# Configuration_Clocking_SRAM.net
KiCad netlist of a schematic drawn in Altium Designer
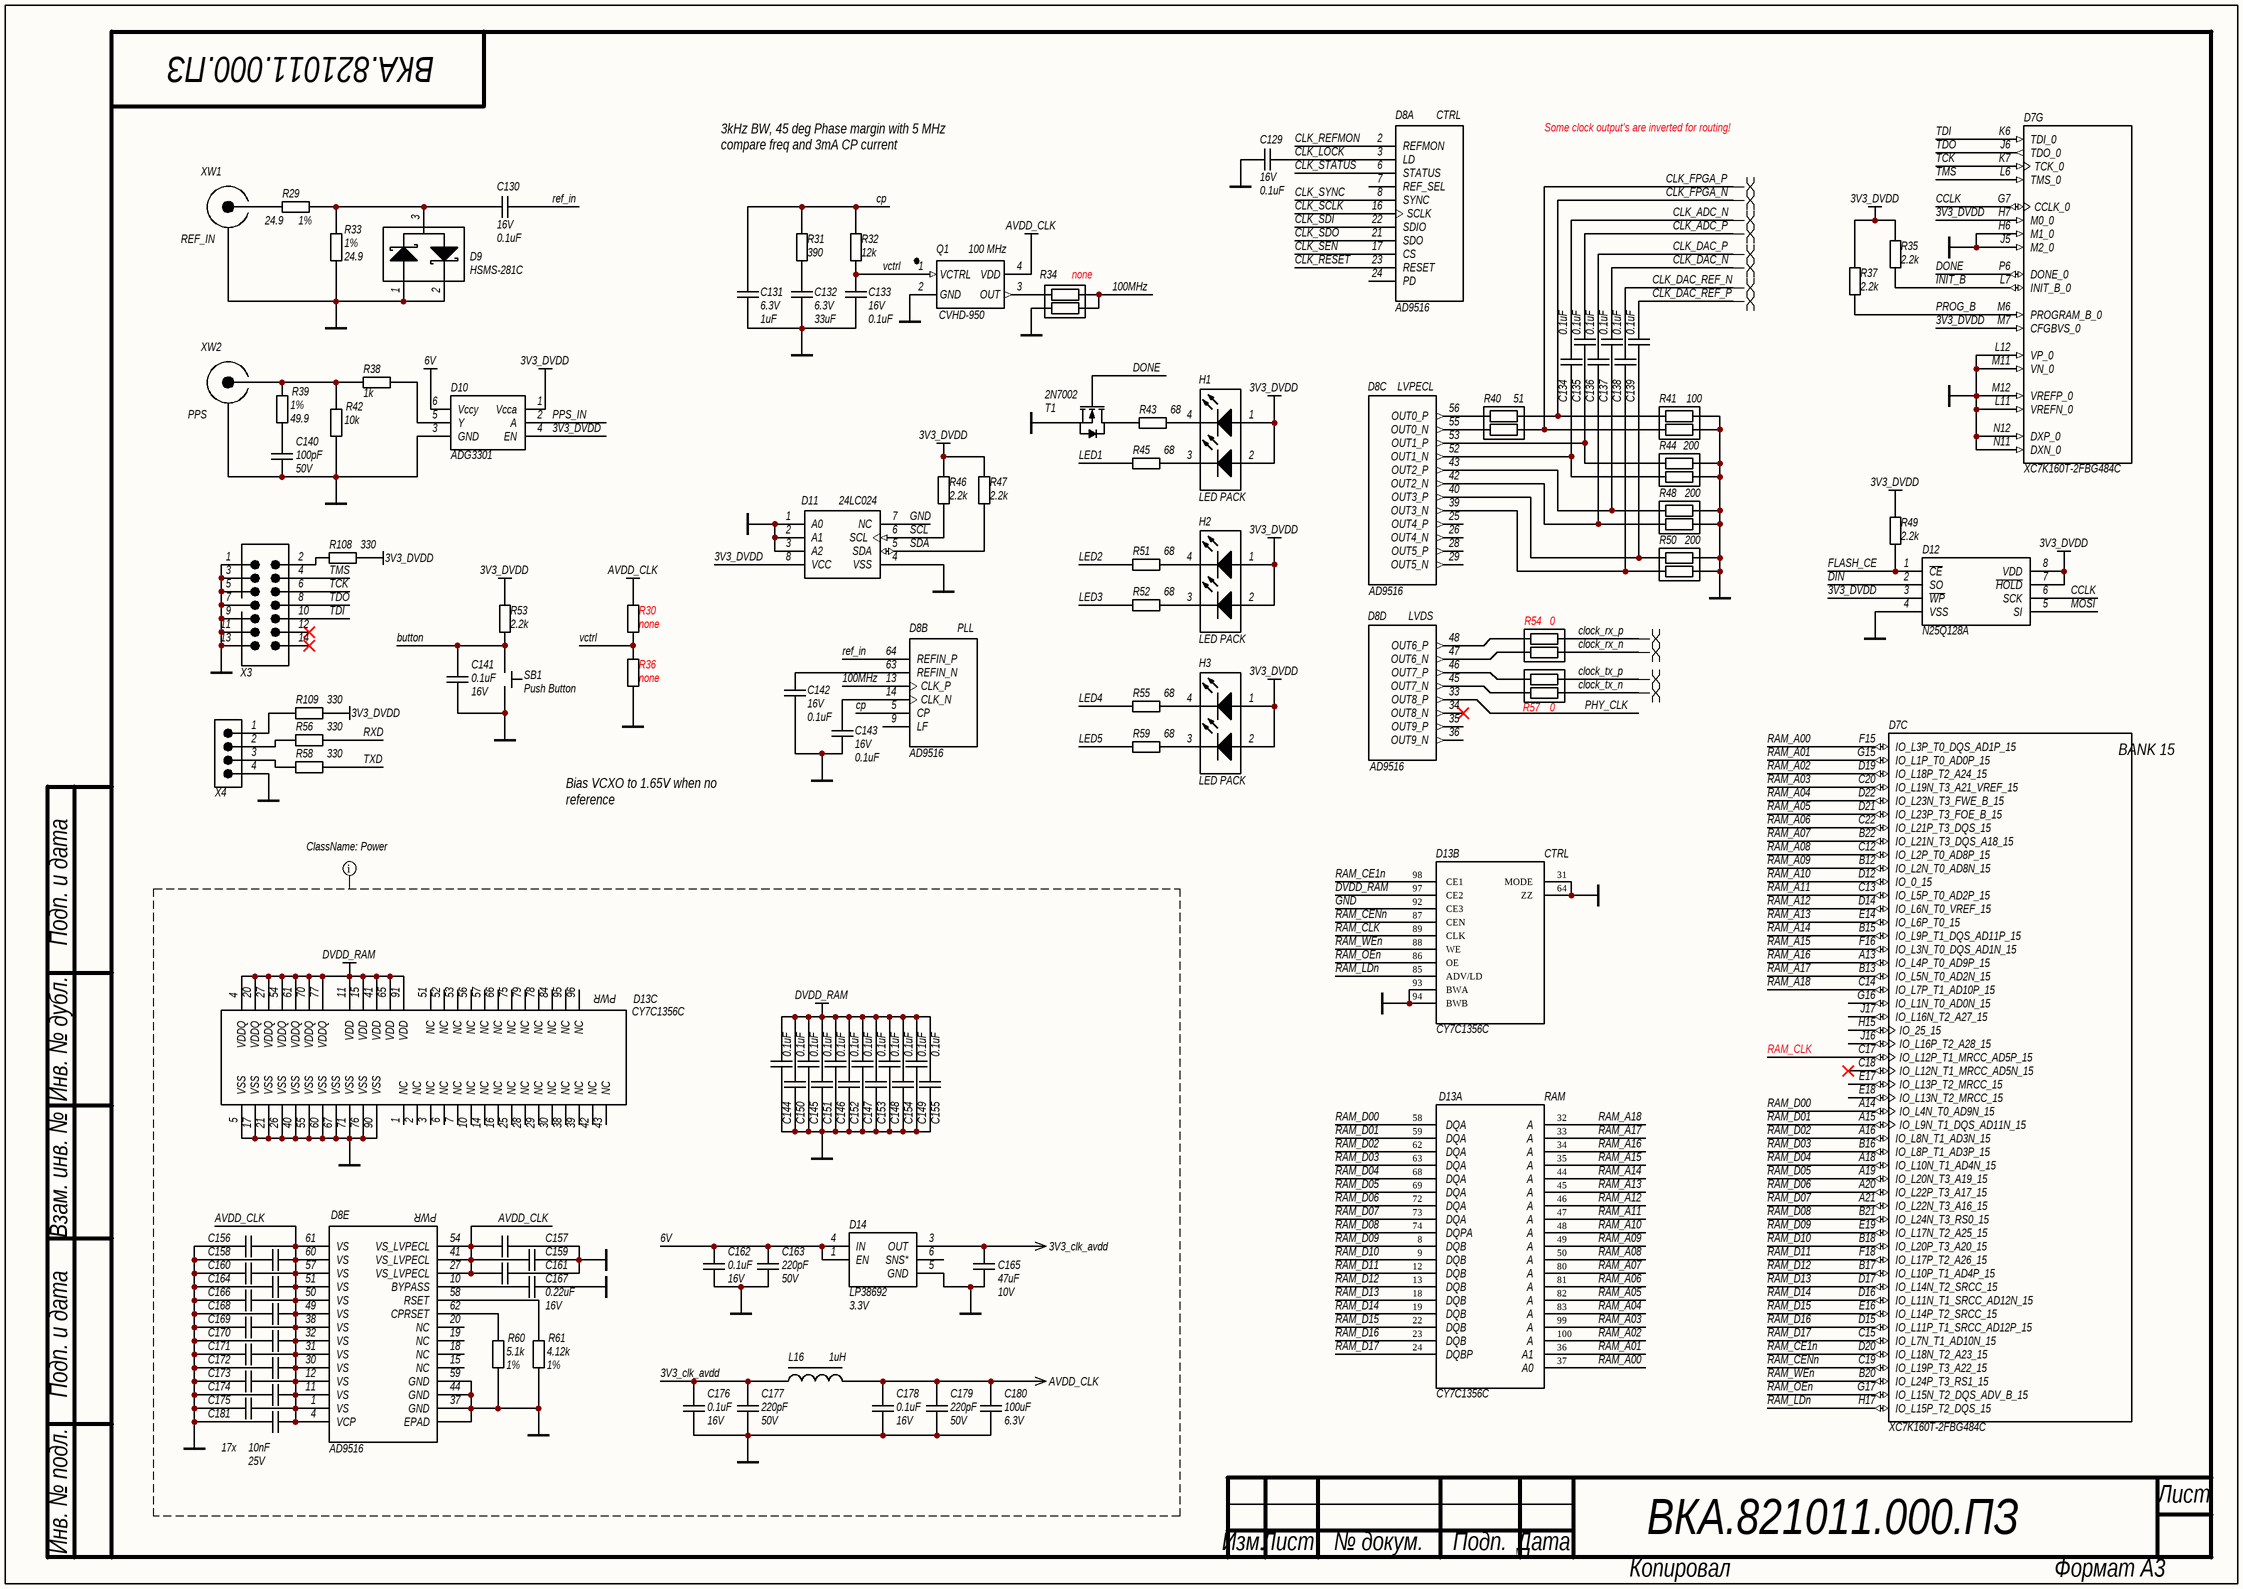
[diagram p0: Configuration&Clocking&SRAM.SchDoc]

(export (version "E")
  (design (tool "Eeschema 10.0.6"))
  (components
    (comp (ref "C129")
      (value "0.1uF")
      (footprint "C0402")
      (description "SMD Capacitor")
      (fields
        (field (name "MANUFACTURER") "Murata")
        (field (name "TOLERANCE") "10%")
        (field (name "VOLTAGE") "16V")
      )
      (libsource (lib "Kintex_SDR") (part "CAP"))
    )
    (comp (ref "C130")
      (value "0.1uF")
      (footprint "C0402")
      (description "SMD Capacitor")
      (fields
        (field (name "MANUFACTURER") "Murata")
        (field (name "TOLERANCE") "10%")
        (field (name "VOLTAGE") "16V")
      )
      (libsource (lib "Kintex_SDR") (part "CAP"))
    )
    (comp (ref "C131")
      (value "1uF")
      (footprint "C0402")
      (description "SMD Capacitor")
      (fields
        (field (name "MANUFACTURER") "Murata")
        (field (name "TOLERANCE") "10%")
        (field (name "VOLTAGE") "6.3V")
      )
      (libsource (lib "Kintex_SDR") (part "CAP"))
    )
    (comp (ref "C132")
      (value "33uF")
      (footprint "C1210")
      (description "SMD Capacitor")
      (fields
        (field (name "MANUFACTURER") "Murata")
        (field (name "TOLERANCE") "10%")
        (field (name "VOLTAGE") "6.3V")
      )
      (libsource (lib "Kintex_SDR") (part "CAP uF"))
    )
    (comp (ref "C133")
      (value "0.1uF")
      (footprint "C0402")
      (description "SMD Capacitor")
      (fields
        (field (name "MANUFACTURER") "Murata")
        (field (name "TOLERANCE") "10%")
        (field (name "VOLTAGE") "16V")
      )
      (libsource (lib "Kintex_SDR") (part "CAP"))
    )
    (comp (ref "C134")
      (value "0.1uF")
      (footprint "C0402")
      (description "SMD Capacitor")
      (fields (field (name "MANUFACTURER") "Murata") (field (name "TOLERANCE") "10%"))
      (libsource (lib "Kintex_SDR") (part "CAP"))
    )
    (comp (ref "C135")
      (value "0.1uF")
      (footprint "C0402")
      (description "SMD Capacitor")
      (fields (field (name "MANUFACTURER") "Murata") (field (name "TOLERANCE") "10%"))
      (libsource (lib "Kintex_SDR") (part "CAP"))
    )
    (comp (ref "C136")
      (value "0.1uF")
      (footprint "C0402")
      (description "SMD Capacitor")
      (fields (field (name "MANUFACTURER") "Murata") (field (name "TOLERANCE") "10%"))
      (libsource (lib "Kintex_SDR") (part "CAP"))
    )
    (comp (ref "C137")
      (value "0.1uF")
      (footprint "C0402")
      (description "SMD Capacitor")
      (fields (field (name "MANUFACTURER") "Murata") (field (name "TOLERANCE") "10%"))
      (libsource (lib "Kintex_SDR") (part "CAP"))
    )
    (comp (ref "C138")
      (value "0.1uF")
      (footprint "C0402")
      (description "SMD Capacitor")
      (fields (field (name "MANUFACTURER") "Murata") (field (name "TOLERANCE") "10%"))
      (libsource (lib "Kintex_SDR") (part "CAP"))
    )
    (comp (ref "C139")
      (value "0.1uF")
      (footprint "C0402")
      (description "SMD Capacitor")
      (fields (field (name "MANUFACTURER") "Murata") (field (name "TOLERANCE") "10%"))
      (libsource (lib "Kintex_SDR") (part "CAP"))
    )
    (comp (ref "C140")
      (value "100pF")
      (footprint "C0603")
      (description "SMD Capacitor")
      (fields
        (field (name "MANUFACTURER") "Murata")
        (field (name "TOLERANCE") "10%")
        (field (name "VOLTAGE") "50V")
      )
      (libsource (lib "Kintex_SDR") (part "CAP"))
    )
    (comp (ref "C141")
      (value "0.1uF")
      (footprint "C0402")
      (description "SMD Capacitor")
      (fields
        (field (name "MANUFACTURER") "Murata")
        (field (name "TOLERANCE") "10%")
        (field (name "VOLTAGE") "16V")
      )
      (libsource (lib "Kintex_SDR") (part "CAP"))
    )
    (comp (ref "C142")
      (value "0.1uF")
      (footprint "C0402")
      (description "SMD Capacitor")
      (fields
        (field (name "MANUFACTURER") "Murata")
        (field (name "TOLERANCE") "10%")
        (field (name "VOLTAGE") "16V")
      )
      (libsource (lib "Kintex_SDR") (part "CAP"))
    )
    (comp (ref "C143")
      (value "0.1uF")
      (footprint "C0402")
      (description "SMD Capacitor")
      (fields
        (field (name "MANUFACTURER") "Murata")
        (field (name "TOLERANCE") "10%")
        (field (name "VOLTAGE") "16V")
      )
      (libsource (lib "Kintex_SDR") (part "CAP"))
    )
    (comp (ref "C144")
      (value "0.1uF")
      (footprint "C0402")
      (description "SMD Capacitor")
      (fields (field (name "MANUFACTURER") "Murata") (field (name "TOLERANCE") "10%"))
      (libsource (lib "Kintex_SDR") (part "CAP"))
    )
    (comp (ref "C145")
      (value "0.1uF")
      (footprint "C0402")
      (description "SMD Capacitor")
      (fields (field (name "MANUFACTURER") "Murata") (field (name "TOLERANCE") "10%"))
      (libsource (lib "Kintex_SDR") (part "CAP"))
    )
    (comp (ref "C146")
      (value "0.1uF")
      (footprint "C0402")
      (description "SMD Capacitor")
      (fields (field (name "MANUFACTURER") "Murata") (field (name "TOLERANCE") "10%"))
      (libsource (lib "Kintex_SDR") (part "CAP"))
    )
    (comp (ref "C147")
      (value "0.1uF")
      (footprint "C0402")
      (description "SMD Capacitor")
      (fields (field (name "MANUFACTURER") "Murata") (field (name "TOLERANCE") "10%"))
      (libsource (lib "Kintex_SDR") (part "CAP"))
    )
    (comp (ref "C148")
      (value "0.1uF")
      (footprint "C0402")
      (description "SMD Capacitor")
      (fields (field (name "MANUFACTURER") "Murata") (field (name "TOLERANCE") "10%"))
      (libsource (lib "Kintex_SDR") (part "CAP"))
    )
    (comp (ref "C149")
      (value "0.1uF")
      (footprint "C0402")
      (description "SMD Capacitor")
      (fields (field (name "MANUFACTURER") "Murata") (field (name "TOLERANCE") "10%"))
      (libsource (lib "Kintex_SDR") (part "CAP"))
    )
    (comp (ref "C150")
      (value "0.1uF")
      (footprint "C0402")
      (description "SMD Capacitor")
      (fields (field (name "MANUFACTURER") "Murata") (field (name "TOLERANCE") "10%"))
      (libsource (lib "Kintex_SDR") (part "CAP"))
    )
    (comp (ref "C151")
      (value "0.1uF")
      (footprint "C0402")
      (description "SMD Capacitor")
      (fields (field (name "MANUFACTURER") "Murata") (field (name "TOLERANCE") "10%"))
      (libsource (lib "Kintex_SDR") (part "CAP"))
    )
    (comp (ref "C152")
      (value "0.1uF")
      (footprint "C0402")
      (description "SMD Capacitor")
      (fields (field (name "MANUFACTURER") "Murata") (field (name "TOLERANCE") "10%"))
      (libsource (lib "Kintex_SDR") (part "CAP"))
    )
    (comp (ref "C153")
      (value "0.1uF")
      (footprint "C0402")
      (description "SMD Capacitor")
      (fields (field (name "MANUFACTURER") "Murata") (field (name "TOLERANCE") "10%"))
      (libsource (lib "Kintex_SDR") (part "CAP"))
    )
    (comp (ref "C154")
      (value "0.1uF")
      (footprint "C0402")
      (description "SMD Capacitor")
      (fields (field (name "MANUFACTURER") "Murata") (field (name "TOLERANCE") "10%"))
      (libsource (lib "Kintex_SDR") (part "CAP"))
    )
    (comp (ref "C155")
      (value "0.1uF")
      (footprint "C0402")
      (description "SMD Capacitor")
      (fields (field (name "MANUFACTURER") "Murata") (field (name "TOLERANCE") "10%"))
      (libsource (lib "Kintex_SDR") (part "CAP"))
    )
    (comp (ref "C156")
      (value "CAP")
      (footprint "C0402")
      (description "SMD Capacitor")
      (fields (field (name "MANUFACTURER") "Murata") (field (name "TOLERANCE") "10%"))
      (libsource (lib "Kintex_SDR") (part "CAP"))
    )
    (comp (ref "C157")
      (value "CAP")
      (footprint "C0402")
      (description "SMD Capacitor")
      (fields (field (name "MANUFACTURER") "Murata") (field (name "TOLERANCE") "10%"))
      (libsource (lib "Kintex_SDR") (part "CAP"))
    )
    (comp (ref "C158")
      (value "CAP")
      (footprint "C0402")
      (description "SMD Capacitor")
      (fields (field (name "MANUFACTURER") "Murata") (field (name "TOLERANCE") "10%"))
      (libsource (lib "Kintex_SDR") (part "CAP"))
    )
    (comp (ref "C159")
      (value "CAP")
      (footprint "C0402")
      (description "SMD Capacitor")
      (fields (field (name "MANUFACTURER") "Murata") (field (name "TOLERANCE") "10%"))
      (libsource (lib "Kintex_SDR") (part "CAP"))
    )
    (comp (ref "C160")
      (value "CAP")
      (footprint "C0402")
      (description "SMD Capacitor")
      (fields (field (name "MANUFACTURER") "Murata") (field (name "TOLERANCE") "10%"))
      (libsource (lib "Kintex_SDR") (part "CAP"))
    )
    (comp (ref "C161")
      (value "CAP")
      (footprint "C0402")
      (description "SMD Capacitor")
      (fields (field (name "MANUFACTURER") "Murata") (field (name "TOLERANCE") "10%"))
      (libsource (lib "Kintex_SDR") (part "CAP"))
    )
    (comp (ref "C162")
      (value "0.1uF")
      (footprint "C0603")
      (description "SMD Capacitor")
      (fields
        (field (name "MANUFACTURER") "Murata")
        (field (name "TOLERANCE") "10%")
        (field (name "VOLTAGE") "16V")
      )
      (libsource (lib "Kintex_SDR") (part "CAP"))
    )
    (comp (ref "C163")
      (value "220pF")
      (footprint "C0603")
      (description "SMD Capacitor")
      (fields
        (field (name "MANUFACTURER") "Murata")
        (field (name "TOLERANCE") "10%")
        (field (name "VOLTAGE") "50V")
      )
      (libsource (lib "Kintex_SDR") (part "CAP"))
    )
    (comp (ref "C164")
      (value "CAP")
      (footprint "C0402")
      (description "SMD Capacitor")
      (fields (field (name "MANUFACTURER") "Murata") (field (name "TOLERANCE") "10%"))
      (libsource (lib "Kintex_SDR") (part "CAP"))
    )
    (comp (ref "C165")
      (value "47uF")
      (footprint "C1210")
      (description "SMD Capacitor")
      (fields
        (field (name "MANUFACTURER") "Murata")
        (field (name "TOLERANCE") "10%")
        (field (name "VOLTAGE") "10V")
      )
      (libsource (lib "Kintex_SDR") (part "CAP uF"))
    )
    (comp (ref "C166")
      (value "CAP")
      (footprint "C0402")
      (description "SMD Capacitor")
      (fields (field (name "MANUFACTURER") "Murata") (field (name "TOLERANCE") "10%"))
      (libsource (lib "Kintex_SDR") (part "CAP"))
    )
    (comp (ref "C167")
      (value "0.22uF")
      (footprint "C0402")
      (description "SMD Capacitor")
      (fields
        (field (name "MANUFACTURER") "Murata")
        (field (name "TOLERANCE") "10%")
        (field (name "VOLTAGE") "16V")
      )
      (libsource (lib "Kintex_SDR") (part "CAP"))
    )
    (comp (ref "C168")
      (value "CAP")
      (footprint "C0402")
      (description "SMD Capacitor")
      (fields (field (name "MANUFACTURER") "Murata") (field (name "TOLERANCE") "10%"))
      (libsource (lib "Kintex_SDR") (part "CAP"))
    )
    (comp (ref "C169")
      (value "CAP")
      (footprint "C0402")
      (description "SMD Capacitor")
      (fields (field (name "MANUFACTURER") "Murata") (field (name "TOLERANCE") "10%"))
      (libsource (lib "Kintex_SDR") (part "CAP"))
    )
    (comp (ref "C170")
      (value "CAP")
      (footprint "C0402")
      (description "SMD Capacitor")
      (fields (field (name "MANUFACTURER") "Murata") (field (name "TOLERANCE") "10%"))
      (libsource (lib "Kintex_SDR") (part "CAP"))
    )
    (comp (ref "C171")
      (value "CAP")
      (footprint "C0402")
      (description "SMD Capacitor")
      (fields (field (name "MANUFACTURER") "Murata") (field (name "TOLERANCE") "10%"))
      (libsource (lib "Kintex_SDR") (part "CAP"))
    )
    (comp (ref "C172")
      (value "CAP")
      (footprint "C0402")
      (description "SMD Capacitor")
      (fields (field (name "MANUFACTURER") "Murata") (field (name "TOLERANCE") "10%"))
      (libsource (lib "Kintex_SDR") (part "CAP"))
    )
    (comp (ref "C173")
      (value "CAP")
      (footprint "C0402")
      (description "SMD Capacitor")
      (fields (field (name "MANUFACTURER") "Murata") (field (name "TOLERANCE") "10%"))
      (libsource (lib "Kintex_SDR") (part "CAP"))
    )
    (comp (ref "C174")
      (value "CAP")
      (footprint "C0402")
      (description "SMD Capacitor")
      (fields (field (name "MANUFACTURER") "Murata") (field (name "TOLERANCE") "10%"))
      (libsource (lib "Kintex_SDR") (part "CAP"))
    )
    (comp (ref "C175")
      (value "CAP")
      (footprint "C0402")
      (description "SMD Capacitor")
      (fields (field (name "MANUFACTURER") "Murata") (field (name "TOLERANCE") "10%"))
      (libsource (lib "Kintex_SDR") (part "CAP"))
    )
    (comp (ref "C176")
      (value "0.1uF")
      (footprint "C0603")
      (description "SMD Capacitor")
      (fields
        (field (name "MANUFACTURER") "Murata")
        (field (name "TOLERANCE") "10%")
        (field (name "VOLTAGE") "16V")
      )
      (libsource (lib "Kintex_SDR") (part "CAP"))
    )
    (comp (ref "C177")
      (value "220pF")
      (footprint "C0603")
      (description "SMD Capacitor")
      (fields
        (field (name "MANUFACTURER") "Murata")
        (field (name "TOLERANCE") "10%")
        (field (name "VOLTAGE") "50V")
      )
      (libsource (lib "Kintex_SDR") (part "CAP"))
    )
    (comp (ref "C178")
      (value "0.1uF")
      (footprint "C0603")
      (description "SMD Capacitor")
      (fields
        (field (name "MANUFACTURER") "Murata")
        (field (name "TOLERANCE") "10%")
        (field (name "VOLTAGE") "16V")
      )
      (libsource (lib "Kintex_SDR") (part "CAP"))
    )
    (comp (ref "C179")
      (value "220pF")
      (footprint "C0603")
      (description "SMD Capacitor")
      (fields
        (field (name "MANUFACTURER") "Murata")
        (field (name "TOLERANCE") "10%")
        (field (name "VOLTAGE") "50V")
      )
      (libsource (lib "Kintex_SDR") (part "CAP"))
    )
    (comp (ref "C180")
      (value "100uF")
      (footprint "C1210")
      (description "SMD Capacitor")
      (fields
        (field (name "MANUFACTURER") "Murata")
        (field (name "TOLERANCE") "20%")
        (field (name "VOLTAGE") "6.3V")
      )
      (libsource (lib "Kintex_SDR") (part "CAP uF"))
    )
    (comp (ref "C181")
      (value "10nF")
      (footprint "C0402")
      (description "SMD Capacitor")
      (fields
        (field (name "MANUFACTURER") "Murata")
        (field (name "TOLERANCE") "10%")
        (field (name "VOLTAGE") "25V")
      )
      (libsource (lib "Kintex_SDR") (part "CAP"))
    )
    (comp (ref "D7")
      (value "XC7K160T-2FBG484C")
      (footprint "FBG484")
      (description "Xilinx 7-Series FPGA")
      (fields (field (name "MANUFACTURER") "Xilinx"))
      (libsource (lib "Kintex_SDR") (part "XC7K160T-2FBG484C"))
    )
    (comp (ref "D8")
      (value "AD9516")
      (footprint "LFCSP-64")
      (description "14-Output Clock Generator")
      (fields (field (name "VOLTAGE") "2.5 V to 3.3 V"))
      (libsource (lib "Kintex_SDR") (part "AD9516"))
    )
    (comp (ref "D9")
      (value "HSMS-281C")
      (footprint "SOT-323")
      (description "RF Schottky Barrier Diodes")
      (libsource (lib "Kintex_SDR") (part "HSMS-281x"))
    )
    (comp (ref "D10")
      (value "ADG3301")
      (footprint "SOT-23-6")
      (description "Bidirectional Logic Level Translator")
      (fields (field (name "VOLTAGE") "1.15 V to 5.5 V"))
      (libsource (lib "Kintex_SDR") (part "ADG3301"))
    )
    (comp (ref "D11")
      (value "24LC024")
      (footprint "SOIC_SN8")
      (description "I2C EEPROM")
      (fields (field (name "MANUFACTURER") "Microchip") (field (name "VOLTAGE") "2.5-5.5V"))
      (libsource (lib "Kintex_SDR") (part "24LC024"))
    )
    (comp (ref "D12")
      (value "N25Q128A")
      (footprint "SOIC8-W")
      (description "SPI Flash")
      (fields (field (name "MANUFACTURER") "Micron Technology") (field (name "VOLTAGE") "2.7-3.6V"))
      (libsource (lib "Kintex_SDR") (part "N25Q128A"))
    )
    (comp (ref "D13")
      (value "CY7C1356C")
      (footprint "TQFP-100")
      (description "Pipelined SRAM with NoBL")
      (fields (field (name "VOLTAGE") "3.3 V"))
      (libsource (lib "Kintex_SDR") (part "CY7C1356C"))
    )
    (comp (ref "D14")
      (value "LP38692")
      (footprint "SOT-223-5")
      (description "Linear Regulator")
      (fields (field (name "VOLTAGE") "3.3V"))
      (libsource (lib "Kintex_SDR") (part "LP38692"))
    )
    (comp (ref "H1")
      (value "LED PACK")
      (footprint "LED_PACK")
      (description "LED Pack For Front Panel")
      (fields (field (name "MANUFACTURER") "Kingbright"))
      (libsource (lib "Kintex_SDR") (part "LED_PACK"))
    )
    (comp (ref "H2")
      (value "LED PACK")
      (footprint "LED_PACK")
      (description "LED Pack For Front Panel")
      (fields (field (name "MANUFACTURER") "Kingbright"))
      (libsource (lib "Kintex_SDR") (part "LED_PACK"))
    )
    (comp (ref "H3")
      (value "LED PACK")
      (footprint "LED_PACK")
      (description "LED Pack For Front Panel")
      (fields (field (name "MANUFACTURER") "Kingbright"))
      (libsource (lib "Kintex_SDR") (part "LED_PACK"))
    )
    (comp (ref "L16")
      (value "1uH")
      (footprint "L1210_Murata")
      (description "Inductor Power Lines")
      (fields (field (name "MANUFACTURER") "Murata") (field (name "TOLERANCE") "5%"))
      (libsource (lib "Kintex_SDR") (part "Inductor LF"))
    )
    (comp (ref "Q1")
      (value "CVHD-950")
      (footprint "CVHD-950")
      (description "Crystal Oscillator")
      (fields (field (name "VOLTAGE") "3.3V ±0.3V") (field (name "FREQUENCY") "100 MHz"))
      (libsource (lib "Kintex_SDR") (part "CVHD-950"))
    )
    (comp (ref "R29")
      (value "24.9")
      (footprint "R0402")
      (description "SMD Resistor")
      (fields
        (field (name "POWER") "0.062 Wt")
        (field (name "TOLERANCE") "1%")
        (field (name "Comment") "RES")
      )
      (libsource (lib "") (part "RES_1"))
    )
    (comp (ref "R30")
      (value "none")
      (footprint "R0402")
      (description "SMD Resistor")
      (fields (field (name "POWER") "0.062 Wt") (field (name "Comment") "RES"))
      (libsource (lib "") (part "RES_2"))
    )
    (comp (ref "R31")
      (value "390")
      (footprint "R0402")
      (description "SMD Resistor")
      (fields (field (name "POWER") "0.062 Wt") (field (name "TOLERANCE") "5%"))
      (libsource (lib "") (part "RES_3"))
    )
    (comp (ref "R32")
      (value "12k")
      (footprint "R0402")
      (description "SMD Resistor")
      (fields (field (name "POWER") "0.062 Wt") (field (name "TOLERANCE") "5%"))
      (libsource (lib "") (part "RES_2"))
    )
    (comp (ref "R33")
      (value "24.9")
      (footprint "R0402")
      (description "SMD Resistor")
      (fields
        (field (name "POWER") "0.062 Wt")
        (field (name "TOLERANCE") "1%")
        (field (name "Comment") "RES")
      )
      (libsource (lib "") (part "RES_2"))
    )
    (comp (ref "R34")
      (value "none")
      (footprint "EX24V")
      (description "Chip Resistor Array")
      (fields (field (name "TOLERANCE") "5%") (field (name "MANUFACTURER") "Panasonic"))
      (libsource (lib "Kintex_SDR") (part "RES 2x0402"))
    )
    (comp (ref "R35")
      (value "2.2k")
      (footprint "R0402")
      (description "SMD Resistor")
      (fields (field (name "POWER") "0.062 Wt") (field (name "TOLERANCE") "5%"))
      (libsource (lib "") (part "RES_2"))
    )
    (comp (ref "R36")
      (value "none")
      (footprint "R0402")
      (description "SMD Resistor")
      (fields (field (name "POWER") "0.062 Wt") (field (name "Comment") "RES"))
      (libsource (lib "") (part "RES_2"))
    )
    (comp (ref "R37")
      (value "2.2k")
      (footprint "R0402")
      (description "SMD Resistor")
      (fields (field (name "POWER") "0.062 Wt") (field (name "TOLERANCE") "5%"))
      (libsource (lib "") (part "RES_2"))
    )
    (comp (ref "R38")
      (value "1k")
      (footprint "R0402")
      (description "SMD Resistor")
      (fields (field (name "POWER") "0.062 Wt") (field (name "TOLERANCE") "5%"))
      (libsource (lib "Kintex_SDR") (part "RES"))
    )
    (comp (ref "R39")
      (value "49.9")
      (footprint "R0402")
      (description "SMD Resistor")
      (fields
        (field (name "POWER") "0.062 Wt")
        (field (name "TOLERANCE") "1%")
        (field (name "Comment") "RES")
      )
      (libsource (lib "") (part "RES_2"))
    )
    (comp (ref "R40")
      (value "51")
      (footprint "EX24V")
      (description "Chip Resistor Array")
      (fields (field (name "TOLERANCE") "5%") (field (name "MANUFACTURER") "Panasonic"))
      (libsource (lib "Kintex_SDR") (part "RES 2x0402"))
    )
    (comp (ref "R41")
      (value "100")
      (footprint "EX24V")
      (description "Chip Resistor Array")
      (fields (field (name "TOLERANCE") "5%") (field (name "MANUFACTURER") "Panasonic"))
      (libsource (lib "Kintex_SDR") (part "RES 2x0402"))
    )
    (comp (ref "R42")
      (value "10k")
      (footprint "R0402")
      (description "SMD Resistor")
      (fields (field (name "POWER") "0.062 Wt") (field (name "TOLERANCE") "5%"))
      (libsource (lib "") (part "RES_2"))
    )
    (comp (ref "R43")
      (value "68")
      (footprint "R0402")
      (description "SMD Resistor")
      (fields (field (name "POWER") "0.062 Wt") (field (name "TOLERANCE") "5%"))
      (libsource (lib "Kintex_SDR") (part "RES"))
    )
    (comp (ref "R44")
      (value "200")
      (footprint "EX24V")
      (description "Chip Resistor Array")
      (fields (field (name "TOLERANCE") "5%") (field (name "MANUFACTURER") "Panasonic"))
      (libsource (lib "") (part "RES 2x0402_1"))
    )
    (comp (ref "R45")
      (value "68")
      (footprint "R0402")
      (description "SMD Resistor")
      (fields (field (name "POWER") "0.062 Wt") (field (name "TOLERANCE") "5%"))
      (libsource (lib "Kintex_SDR") (part "RES"))
    )
    (comp (ref "R46")
      (value "2.2k")
      (footprint "R0402")
      (description "SMD Resistor")
      (fields (field (name "POWER") "0.062 Wt") (field (name "TOLERANCE") "5%"))
      (libsource (lib "") (part "RES_2"))
    )
    (comp (ref "R47")
      (value "2.2k")
      (footprint "R0402")
      (description "SMD Resistor")
      (fields (field (name "POWER") "0.062 Wt") (field (name "TOLERANCE") "5%"))
      (libsource (lib "") (part "RES_2"))
    )
    (comp (ref "R48")
      (value "200")
      (footprint "EX24V")
      (description "Chip Resistor Array")
      (fields (field (name "TOLERANCE") "5%") (field (name "MANUFACTURER") "Panasonic"))
      (libsource (lib "") (part "RES 2x0402_1"))
    )
    (comp (ref "R49")
      (value "2.2k")
      (footprint "R0402")
      (description "SMD Resistor")
      (fields (field (name "POWER") "0.062 Wt") (field (name "TOLERANCE") "5%"))
      (libsource (lib "") (part "RES_2"))
    )
    (comp (ref "R50")
      (value "200")
      (footprint "EX24V")
      (description "Chip Resistor Array")
      (fields (field (name "TOLERANCE") "5%") (field (name "MANUFACTURER") "Panasonic"))
      (libsource (lib "") (part "RES 2x0402_1"))
    )
    (comp (ref "R51")
      (value "68")
      (footprint "R0402")
      (description "SMD Resistor")
      (fields (field (name "POWER") "0.062 Wt") (field (name "TOLERANCE") "5%"))
      (libsource (lib "Kintex_SDR") (part "RES"))
    )
    (comp (ref "R52")
      (value "68")
      (footprint "R0402")
      (description "SMD Resistor")
      (fields (field (name "POWER") "0.062 Wt") (field (name "TOLERANCE") "5%"))
      (libsource (lib "Kintex_SDR") (part "RES"))
    )
    (comp (ref "R53")
      (value "2.2k")
      (footprint "R0402")
      (description "SMD Resistor")
      (fields (field (name "POWER") "0.062 Wt") (field (name "TOLERANCE") "5%"))
      (libsource (lib "") (part "RES_2"))
    )
    (comp (ref "R54")
      (value "0")
      (footprint "EX24V")
      (description "Chip Resistor Array")
      (fields (field (name "MANUFACTURER") "Panasonic") (field (name "Comment") "RES 2x0402"))
      (libsource (lib "Kintex_SDR") (part "RES 2x0402"))
    )
    (comp (ref "R55")
      (value "68")
      (footprint "R0402")
      (description "SMD Resistor")
      (fields (field (name "POWER") "0.062 Wt") (field (name "TOLERANCE") "5%"))
      (libsource (lib "Kintex_SDR") (part "RES"))
    )
    (comp (ref "R56")
      (value "330")
      (footprint "R0402")
      (description "SMD Resistor")
      (fields (field (name "POWER") "0.062 Wt") (field (name "TOLERANCE") "5%"))
      (libsource (lib "Kintex_SDR") (part "RES"))
    )
    (comp (ref "R57")
      (value "0")
      (footprint "EX24V")
      (description "Chip Resistor Array")
      (fields (field (name "MANUFACTURER") "Panasonic") (field (name "Comment") "RES 2x0402"))
      (libsource (lib "Kintex_SDR") (part "RES 2x0402"))
    )
    (comp (ref "R58")
      (value "330")
      (footprint "R0402")
      (description "SMD Resistor")
      (fields (field (name "POWER") "0.062 Wt") (field (name "TOLERANCE") "5%"))
      (libsource (lib "Kintex_SDR") (part "RES"))
    )
    (comp (ref "R59")
      (value "68")
      (footprint "R0402")
      (description "SMD Resistor")
      (fields (field (name "POWER") "0.062 Wt") (field (name "TOLERANCE") "5%"))
      (libsource (lib "Kintex_SDR") (part "RES"))
    )
    (comp (ref "R60")
      (value "5.1k")
      (footprint "R0402")
      (description "SMD Resistor")
      (fields
        (field (name "POWER") "0.062 Wt")
        (field (name "TOLERANCE") "1%")
        (field (name "Comment") "RES")
      )
      (libsource (lib "") (part "RES_2"))
    )
    (comp (ref "R61")
      (value "4.12k")
      (footprint "R0402")
      (description "SMD Resistor")
      (fields
        (field (name "POWER") "0.062 Wt")
        (field (name "TOLERANCE") "1%")
        (field (name "Comment") "RES")
      )
      (libsource (lib "") (part "RES_2"))
    )
    (comp (ref "R108")
      (value "330")
      (footprint "R0402")
      (description "SMD Resistor")
      (fields (field (name "POWER") "0.062 Wt") (field (name "TOLERANCE") "5%"))
      (libsource (lib "Kintex_SDR") (part "RES"))
    )
    (comp (ref "R109")
      (value "330")
      (footprint "R0402")
      (description "SMD Resistor")
      (fields (field (name "POWER") "0.062 Wt") (field (name "TOLERANCE") "5%"))
      (libsource (lib "Kintex_SDR") (part "RES"))
    )
    (comp (ref "SB1")
      (value "Push Button")
      (footprint "B3FS-1000")
      (description "Tactile Switch (SMT)")
      (fields (field (name "MANUFACTURER") "Omron") (field (name "VOLTAGE") "24V"))
      (libsource (lib "Kintex_SDR") (part "Button"))
    )
    (comp (ref "T1")
      (value "2N7002")
      (footprint "SOT-23")
      (description "N-Channel MOSFET 2N7002")
      (fields (field (name "VOLTAGE") "60V"))
      (libsource (lib "Kintex_SDR") (part "2N7002"))
    )
    (comp (ref "X3")
      (value "HDR Debug_14-pin")
      (footprint "JTAG Header 14-pin")
      (description "14-pin 2.54mm pitch PCB Header")
      (libsource (lib "Kintex_SDR") (part "HDR Debug_14-pin"))
    )
    (comp (ref "X4")
      (value "HDR 4-way")
      (footprint "Right Angle Male Header")
      (description "4-way Angle PCB Header")
      (libsource (lib "Kintex_SDR") (part "HDR 4-way"))
    )
    (comp (ref "XW1")
      (value "REF_IN")
      (footprint "SMA Angle Female")
      (description "SMA Male Right-Angle PCM Connector")
      (fields (field (name "MANUFACTURER") "Molex"))
      (libsource (lib "Kintex_SDR") (part "SMA RF Connector"))
    )
    (comp (ref "XW2")
      (value "PPS")
      (footprint "SMA Angle Female")
      (description "SMA Male Right-Angle PCM Connector")
      (fields (field (name "MANUFACTURER") "Molex"))
      (libsource (lib "Kintex_SDR") (part "SMA RF Connector"))
    )
  )
  (nets
    (net (code "1") (name "/100MHz") (class "Default")
      (node (ref "D8") (pin "13") (pinfunction "CLK_P_13") (pintype "passive"))
      (node (ref "R34") (pin "3") (pinfunction "3_3") (pintype "passive"))
      (node (ref "R34") (pin "4") (pinfunction "4_4") (pintype "passive"))
    )
    (net (code "2") (name "/CCLK") (class "Default")
      (node (ref "D12") (pin "6") (pinfunction "SCK_6") (pintype "passive"))
      (node (ref "D7") (pin "G7") (pinfunction "CCLK_0_G7") (pintype "bidirectional"))
    )
    (net (code "3") (name "/CLK_ADC_N") (class "Default")
      (node (ref "C134") (pin "1") (pinfunction "1_1") (pintype "passive"))
    )
    (net (code "4") (name "/CLK_ADC_P") (class "Default")
      (node (ref "C135") (pin "1") (pinfunction "1_1") (pintype "passive"))
    )
    (net (code "5") (name "/CLK_DAC_N") (class "Default")
      (node (ref "C137") (pin "1") (pinfunction "1_1") (pintype "passive"))
    )
    (net (code "6") (name "/CLK_DAC_P") (class "Default")
      (node (ref "C136") (pin "1") (pinfunction "1_1") (pintype "passive"))
    )
    (net (code "7") (name "/CLK_DAC_REF_N") (class "Default")
      (node (ref "C138") (pin "1") (pinfunction "1_1") (pintype "passive"))
    )
    (net (code "8") (name "/CLK_DAC_REF_P") (class "Default")
      (node (ref "C139") (pin "1") (pinfunction "1_1") (pintype "passive"))
    )
    (net (code "9") (name "/CLK_FPGA_N") (class "Default")
      (node (ref "R40") (pin "4") (pinfunction "4_4") (pintype "passive"))
      (node (ref "R41") (pin "1") (pinfunction "1_1") (pintype "passive"))
    )
    (net (code "10") (name "/CLK_FPGA_P") (class "Default")
      (node (ref "R40") (pin "3") (pinfunction "3_3") (pintype "passive"))
      (node (ref "R41") (pin "2") (pinfunction "2_2") (pintype "passive"))
    )
    (net (code "11") (name "/CLK_LOCK") (class "Default")
      (node (ref "C129") (pin "1") (pinfunction "1_1") (pintype "passive"))
      (node (ref "D8") (pin "3") (pinfunction "LD_3") (pintype "passive"))
    )
    (net (code "12") (name "/CLK_REFMON") (class "Default")
      (node (ref "D8") (pin "2") (pinfunction "REFMON_2") (pintype "passive"))
    )
    (net (code "13") (name "/CLK_RESET") (class "Default")
      (node (ref "D8") (pin "23") (pinfunction "RESET_23") (pintype "passive"))
    )
    (net (code "14") (name "/CLK_SCLK") (class "Default")
      (node (ref "D8") (pin "16") (pinfunction "SCLK_16") (pintype "passive"))
    )
    (net (code "15") (name "/CLK_SDI") (class "Default")
      (node (ref "D8") (pin "22") (pinfunction "SDIO_22") (pintype "passive"))
    )
    (net (code "16") (name "/CLK_SDO") (class "Default")
      (node (ref "D8") (pin "21") (pinfunction "SDO_21") (pintype "passive"))
    )
    (net (code "17") (name "/CLK_SEN") (class "Default")
      (node (ref "D8") (pin "17") (pinfunction "CS_17") (pintype "passive"))
    )
    (net (code "18") (name "/CLK_STATUS") (class "Default")
      (node (ref "D8") (pin "6") (pinfunction "STATUS_6") (pintype "passive"))
    )
    (net (code "19") (name "/CLK_SYNC") (class "Default")
      (node (ref "D8") (pin "8") (pinfunction "SYNC_8") (pintype "passive"))
    )
    (net (code "20") (name "/DIN") (class "Default")
      (node (ref "D12") (pin "2") (pinfunction "SO_2") (pintype "passive"))
    )
    (net (code "21") (name "/DONE") (class "Default")
      (node (ref "D7") (pin "P6") (pinfunction "DONE_0_P6") (pintype "bidirectional"))
      (node (ref "T1") (pin "1") (pinfunction "G_1") (pintype "passive"))
    )
    (net (code "22") (name "/FLASH_CE") (class "Default")
      (node (ref "D12") (pin "1") (pinfunction "~{CE}_1") (pintype "passive"))
      (node (ref "R49") (pin "1") (pinfunction "1_1") (pintype "passive"))
    )
    (net (code "23") (name "/INIT_B") (class "Default")
      (node (ref "D7") (pin "L7") (pinfunction "INIT_B_0_L7") (pintype "bidirectional"))
      (node (ref "R35") (pin "1") (pinfunction "1_1") (pintype "passive"))
    )
    (net (code "24") (name "/LED1") (class "Default")
      (node (ref "R45") (pin "2") (pinfunction "2_2") (pintype "passive"))
    )
    (net (code "25") (name "/LED2") (class "Default")
      (node (ref "R51") (pin "2") (pinfunction "2_2") (pintype "passive"))
    )
    (net (code "26") (name "/LED3") (class "Default")
      (node (ref "R52") (pin "2") (pinfunction "2_2") (pintype "passive"))
    )
    (net (code "27") (name "/LED4") (class "Default")
      (node (ref "R55") (pin "2") (pinfunction "2_2") (pintype "passive"))
    )
    (net (code "28") (name "/LED5") (class "Default")
      (node (ref "R59") (pin "2") (pinfunction "2_2") (pintype "passive"))
    )
    (net (code "29") (name "/MOSI") (class "Default")
      (node (ref "D12") (pin "5") (pinfunction "SI_5") (pintype "passive"))
    )
    (net (code "30") (name "/PHY_CLK") (class "Default")
      (node (ref "D8") (pin "33") (pinfunction "OUT8_P_33") (pintype "output"))
    )
    (net (code "31") (name "/PPS_IN") (class "Default")
      (node (ref "D10") (pin "2") (pinfunction "A_2") (pintype "passive"))
    )
    (net (code "32") (name "/PROG_B") (class "Default")
      (node (ref "D7") (pin "M6") (pinfunction "PROGRAM_B_0_M6") (pintype "input"))
      (node (ref "R37") (pin "1") (pinfunction "1_1") (pintype "passive"))
    )
    (net (code "33") (name "/RAM_A00") (class "Default")
      (node (ref "D13") (pin "37") (pinfunction "A0_37") (pintype "passive"))
      (node (ref "D7") (pin "F15") (pinfunction "IO_L3P_T0_DQS_AD1P_15_F15") (pintype "bidirectional"))
    )
    (net (code "34") (name "/RAM_A01") (class "Default")
      (node (ref "D13") (pin "36") (pinfunction "A1_36") (pintype "passive"))
      (node (ref "D7") (pin "G15") (pinfunction "IO_L1P_T0_AD0P_15_G15") (pintype "bidirectional"))
    )
    (net (code "35") (name "/RAM_A02") (class "Default")
      (node (ref "D13") (pin "100") (pinfunction "A_100") (pintype "passive"))
      (node (ref "D7") (pin "D19") (pinfunction "IO_L18P_T2_A24_15_D19") (pintype "bidirectional"))
    )
    (net (code "36") (name "/RAM_A03") (class "Default")
      (node (ref "D13") (pin "99") (pinfunction "A_99") (pintype "passive"))
      (node (ref "D7") (pin "C20") (pinfunction "IO_L19N_T3_A21_VREF_15_C20") (pintype "bidirectional"))
    )
    (net (code "37") (name "/RAM_A04") (class "Default")
      (node (ref "D13") (pin "83") (pinfunction "A_83") (pintype "passive"))
      (node (ref "D7") (pin "D22") (pinfunction "IO_L23N_T3_FWE_B_15_D22") (pintype "bidirectional"))
    )
    (net (code "38") (name "/RAM_A05") (class "Default")
      (node (ref "D13") (pin "82") (pinfunction "A_82") (pintype "passive"))
      (node (ref "D7") (pin "D21") (pinfunction "IO_L23P_T3_FOE_B_15_D21") (pintype "bidirectional"))
    )
    (net (code "39") (name "/RAM_A06") (class "Default")
      (node (ref "D13") (pin "81") (pinfunction "A_81") (pintype "passive"))
      (node (ref "D7") (pin "C22") (pinfunction "IO_L21P_T3_DQS_15_C22") (pintype "bidirectional"))
    )
    (net (code "40") (name "/RAM_A07") (class "Default")
      (node (ref "D13") (pin "80") (pinfunction "A_80") (pintype "passive"))
      (node (ref "D7") (pin "B22") (pinfunction "IO_L21N_T3_DQS_A18_15_B22") (pintype "bidirectional"))
    )
    (net (code "41") (name "/RAM_A08") (class "Default")
      (node (ref "D13") (pin "50") (pinfunction "A_50") (pintype "passive"))
      (node (ref "D7") (pin "C12") (pinfunction "IO_L2P_T0_AD8P_15_C12") (pintype "bidirectional"))
    )
    (net (code "42") (name "/RAM_A09") (class "Default")
      (node (ref "D13") (pin "49") (pinfunction "A_49") (pintype "passive"))
      (node (ref "D7") (pin "B12") (pinfunction "IO_L2N_T0_AD8N_15_B12") (pintype "bidirectional"))
    )
    (net (code "43") (name "/RAM_A10") (class "Default")
      (node (ref "D13") (pin "48") (pinfunction "A_48") (pintype "passive"))
      (node (ref "D7") (pin "D12") (pinfunction "IO_0_15_D12") (pintype "bidirectional"))
    )
    (net (code "44") (name "/RAM_A11") (class "Default")
      (node (ref "D13") (pin "47") (pinfunction "A_47") (pintype "passive"))
      (node (ref "D7") (pin "C13") (pinfunction "IO_L5P_T0_AD2P_15_C13") (pintype "bidirectional"))
    )
    (net (code "45") (name "/RAM_A12") (class "Default")
      (node (ref "D13") (pin "46") (pinfunction "A_46") (pintype "passive"))
      (node (ref "D7") (pin "D14") (pinfunction "IO_L6N_T0_VREF_15_D14") (pintype "bidirectional"))
    )
    (net (code "46") (name "/RAM_A13") (class "Default")
      (node (ref "D13") (pin "45") (pinfunction "A_45") (pintype "passive"))
      (node (ref "D7") (pin "E14") (pinfunction "IO_L6P_T0_15_E14") (pintype "bidirectional"))
    )
    (net (code "47") (name "/RAM_A14") (class "Default")
      (node (ref "D13") (pin "44") (pinfunction "A_44") (pintype "passive"))
      (node (ref "D7") (pin "B15") (pinfunction "IO_L9P_T1_DQS_AD11P_15_B15") (pintype "bidirectional"))
    )
    (net (code "48") (name "/RAM_A15") (class "Default")
      (node (ref "D13") (pin "35") (pinfunction "A_35") (pintype "passive"))
      (node (ref "D7") (pin "F16") (pinfunction "IO_L3N_T0_DQS_AD1N_15_F16") (pintype "bidirectional"))
    )
    (net (code "49") (name "/RAM_A16") (class "Default")
      (node (ref "D13") (pin "34") (pinfunction "A_34") (pintype "passive"))
      (node (ref "D7") (pin "A13") (pinfunction "IO_L4P_T0_AD9P_15_A13") (pintype "bidirectional"))
    )
    (net (code "50") (name "/RAM_A17") (class "Default")
      (node (ref "D13") (pin "33") (pinfunction "A_33") (pintype "passive"))
      (node (ref "D7") (pin "B13") (pinfunction "IO_L5N_T0_AD2N_15_B13") (pintype "bidirectional"))
    )
    (net (code "51") (name "/RAM_A18") (class "Default")
      (node (ref "D13") (pin "32") (pinfunction "A_32") (pintype "passive"))
      (node (ref "D7") (pin "C14") (pinfunction "IO_L7P_T1_AD10P_15_C14") (pintype "bidirectional"))
    )
    (net (code "52") (name "/RAM_CE1n") (class "Default")
      (node (ref "D13") (pin "98") (pinfunction "CE1_98") (pintype "passive"))
      (node (ref "D7") (pin "D20") (pinfunction "IO_L18N_T2_A23_15_D20") (pintype "bidirectional"))
    )
    (net (code "53") (name "/RAM_CENn") (class "Default")
      (node (ref "D13") (pin "87") (pinfunction "CEN_87") (pintype "passive"))
      (node (ref "D7") (pin "C19") (pinfunction "IO_L19P_T3_A22_15_C19") (pintype "bidirectional"))
    )
    (net (code "54") (name "/RAM_CLK") (class "Default")
      (node (ref "D13") (pin "89") (pinfunction "CLK_89") (pintype "passive"))
      (node (ref "D7") (pin "C17") (pinfunction "IO_L12P_T1_MRCC_AD5P_15_C17") (pintype "bidirectional"))
    )
    (net (code "55") (name "/RAM_D00") (class "Default")
      (node (ref "D13") (pin "58") (pinfunction "DQA_58") (pintype "passive"))
      (node (ref "D7") (pin "A14") (pinfunction "IO_L4N_T0_AD9N_15_A14") (pintype "bidirectional"))
    )
    (net (code "56") (name "/RAM_D01") (class "Default")
      (node (ref "D13") (pin "59") (pinfunction "DQA_59") (pintype "passive"))
      (node (ref "D7") (pin "A15") (pinfunction "IO_L9N_T1_DQS_AD11N_15_A15") (pintype "bidirectional"))
    )
    (net (code "57") (name "/RAM_D02") (class "Default")
      (node (ref "D13") (pin "62") (pinfunction "DQA_62") (pintype "passive"))
      (node (ref "D7") (pin "A16") (pinfunction "IO_L8N_T1_AD3N_15_A16") (pintype "bidirectional"))
    )
    (net (code "58") (name "/RAM_D03") (class "Default")
      (node (ref "D13") (pin "63") (pinfunction "DQA_63") (pintype "passive"))
      (node (ref "D7") (pin "B16") (pinfunction "IO_L8P_T1_AD3P_15_B16") (pintype "bidirectional"))
    )
    (net (code "59") (name "/RAM_D04") (class "Default")
      (node (ref "D13") (pin "68") (pinfunction "DQA_68") (pintype "passive"))
      (node (ref "D7") (pin "A18") (pinfunction "IO_L10N_T1_AD4N_15_A18") (pintype "bidirectional"))
    )
    (net (code "60") (name "/RAM_D05") (class "Default")
      (node (ref "D13") (pin "69") (pinfunction "DQA_69") (pintype "passive"))
      (node (ref "D7") (pin "A19") (pinfunction "IO_L20N_T3_A19_15_A19") (pintype "bidirectional"))
    )
    (net (code "61") (name "/RAM_D06") (class "Default")
      (node (ref "D13") (pin "72") (pinfunction "DQA_72") (pintype "passive"))
      (node (ref "D7") (pin "A20") (pinfunction "IO_L22P_T3_A17_15_A20") (pintype "bidirectional"))
    )
    (net (code "62") (name "/RAM_D07") (class "Default")
      (node (ref "D13") (pin "73") (pinfunction "DQA_73") (pintype "passive"))
      (node (ref "D7") (pin "A21") (pinfunction "IO_L22N_T3_A16_15_A21") (pintype "bidirectional"))
    )
    (net (code "63") (name "/RAM_D08") (class "Default")
      (node (ref "D13") (pin "74") (pinfunction "DQPA_74") (pintype "passive"))
      (node (ref "D7") (pin "B21") (pinfunction "IO_L24N_T3_RS0_15_B21") (pintype "bidirectional"))
    )
    (net (code "64") (name "/RAM_D09") (class "Default")
      (node (ref "D13") (pin "8") (pinfunction "DQB_8") (pintype "passive"))
      (node (ref "D7") (pin "E19") (pinfunction "IO_L17N_T2_A25_15_E19") (pintype "bidirectional"))
    )
    (net (code "65") (name "/RAM_D10") (class "Default")
      (node (ref "D13") (pin "9") (pinfunction "DQB_9") (pintype "passive"))
      (node (ref "D7") (pin "B18") (pinfunction "IO_L20P_T3_A20_15_B18") (pintype "bidirectional"))
    )
    (net (code "66") (name "/RAM_D11") (class "Default")
      (node (ref "D13") (pin "12") (pinfunction "DQB_12") (pintype "passive"))
      (node (ref "D7") (pin "F18") (pinfunction "IO_L17P_T2_A26_15_F18") (pintype "bidirectional"))
    )
    (net (code "67") (name "/RAM_D12") (class "Default")
      (node (ref "D13") (pin "13") (pinfunction "DQB_13") (pintype "passive"))
      (node (ref "D7") (pin "B17") (pinfunction "IO_L10P_T1_AD4P_15_B17") (pintype "bidirectional"))
    )
    (net (code "68") (name "/RAM_D13") (class "Default")
      (node (ref "D13") (pin "18") (pinfunction "DQB_18") (pintype "passive"))
      (node (ref "D7") (pin "D17") (pinfunction "IO_L14N_T2_SRCC_15_D17") (pintype "bidirectional"))
    )
    (net (code "69") (name "/RAM_D14") (class "Default")
      (node (ref "D13") (pin "19") (pinfunction "DQB_19") (pintype "passive"))
      (node (ref "D7") (pin "D16") (pinfunction "IO_L11N_T1_SRCC_AD12N_15_D16") (pintype "bidirectional"))
    )
    (net (code "70") (name "/RAM_D15") (class "Default")
      (node (ref "D13") (pin "22") (pinfunction "DQB_22") (pintype "passive"))
      (node (ref "D7") (pin "E16") (pinfunction "IO_L14P_T2_SRCC_15_E16") (pintype "bidirectional"))
    )
    (net (code "71") (name "/RAM_D16") (class "Default")
      (node (ref "D13") (pin "23") (pinfunction "DQB_23") (pintype "passive"))
      (node (ref "D7") (pin "D15") (pinfunction "IO_L11P_T1_SRCC_AD12P_15_D15") (pintype "bidirectional"))
    )
    (net (code "72") (name "/RAM_D17") (class "Default")
      (node (ref "D13") (pin "24") (pinfunction "DQBP_24") (pintype "passive"))
      (node (ref "D7") (pin "C15") (pinfunction "IO_L7N_T1_AD10N_15_C15") (pintype "bidirectional"))
    )
    (net (code "73") (name "/RAM_LDn") (class "Default")
      (node (ref "D13") (pin "85") (pinfunction "ADV/LD_85") (pintype "passive"))
      (node (ref "D7") (pin "H17") (pinfunction "IO_L15P_T2_DQS_15_H17") (pintype "bidirectional"))
    )
    (net (code "74") (name "/RAM_OEn") (class "Default")
      (node (ref "D13") (pin "86") (pinfunction "OE_86") (pintype "passive"))
      (node (ref "D7") (pin "G17") (pinfunction "IO_L15N_T2_DQS_ADV_B_15_G17") (pintype "bidirectional"))
    )
    (net (code "75") (name "/RAM_WEn") (class "Default")
      (node (ref "D13") (pin "88") (pinfunction "WE_88") (pintype "passive"))
      (node (ref "D7") (pin "B20") (pinfunction "IO_L24P_T3_RS1_15_B20") (pintype "bidirectional"))
    )
    (net (code "76") (name "/RXD") (class "Default")
      (node (ref "R56") (pin "1") (pinfunction "1_1") (pintype "passive"))
    )
    (net (code "77") (name "/SCL") (class "Default")
      (node (ref "D11") (pin "6") (pinfunction "SCL_6") (pintype "input"))
      (node (ref "R46") (pin "1") (pinfunction "1_1") (pintype "passive"))
    )
    (net (code "78") (name "/SDA") (class "Default")
      (node (ref "D11") (pin "5") (pinfunction "SDA_5") (pintype "bidirectional"))
      (node (ref "R47") (pin "1") (pinfunction "1_1") (pintype "passive"))
    )
    (net (code "79") (name "/TCK") (class "Default")
      (node (ref "D7") (pin "K7") (pinfunction "TCK_0_K7") (pintype "input"))
      (node (ref "X3") (pin "6") (pinfunction "TCK_6") (pintype "passive"))
    )
    (net (code "80") (name "/TDI") (class "Default")
      (node (ref "D7") (pin "K6") (pinfunction "TDI_0_K6") (pintype "input"))
      (node (ref "X3") (pin "10") (pinfunction "TDI_10") (pintype "passive"))
    )
    (net (code "81") (name "/TDO") (class "Default")
      (node (ref "D7") (pin "J6") (pinfunction "TDO_0_J6") (pintype "output"))
      (node (ref "X3") (pin "8") (pinfunction "TDO_8") (pintype "passive"))
    )
    (net (code "82") (name "/TMS") (class "Default")
      (node (ref "D7") (pin "L6") (pinfunction "TMS_0_L6") (pintype "input"))
      (node (ref "X3") (pin "4") (pinfunction "TMS_4") (pintype "passive"))
    )
    (net (code "83") (name "/TXD") (class "Default")
      (node (ref "R58") (pin "1") (pinfunction "1_1") (pintype "passive"))
    )
    (net (code "84") (name "/button") (class "Default")
      (node (ref "C141") (pin "2") (pinfunction "2_2") (pintype "passive"))
      (node (ref "R53") (pin "1") (pinfunction "1_1") (pintype "passive"))
      (node (ref "SB1") (pin "1") (pinfunction "1_1") (pintype "passive"))
    )
    (net (code "85") (name "/clock_rx_n") (class "Default")
      (node (ref "R54") (pin "3") (pinfunction "3_3") (pintype "passive"))
    )
    (net (code "86") (name "/clock_rx_p") (class "Default")
      (node (ref "R54") (pin "4") (pinfunction "4_4") (pintype "passive"))
    )
    (net (code "87") (name "/clock_tx_n") (class "Default")
      (node (ref "R57") (pin "3") (pinfunction "3_3") (pintype "passive"))
    )
    (net (code "88") (name "/clock_tx_p") (class "Default")
      (node (ref "R57") (pin "4") (pinfunction "4_4") (pintype "passive"))
    )
    (net (code "89") (name "/cp") (class "Default")
      (node (ref "C131") (pin "1") (pinfunction "1_1") (pintype "passive"))
      (node (ref "D8") (pin "5") (pinfunction "CP_5") (pintype "passive"))
      (node (ref "R31") (pin "1") (pinfunction "1_1") (pintype "passive"))
      (node (ref "R32") (pin "2") (pinfunction "2_2") (pintype "passive"))
    )
    (net (code "90") (name "/ref_in") (class "Default")
      (node (ref "C130") (pin "1") (pinfunction "1_1") (pintype "passive"))
      (node (ref "D8") (pin "64") (pinfunction "REFIN_P_64") (pintype "passive"))
    )
    (net (code "91") (name "/vctrl") (class "Default")
      (node (ref "C133") (pin "1") (pinfunction "1_1") (pintype "passive"))
      (node (ref "Q1") (pin "1") (pinfunction "VCTRL_1") (pintype "input"))
      (node (ref "R30") (pin "1") (pinfunction "1_1") (pintype "passive"))
      (node (ref "R32") (pin "1") (pinfunction "1_1") (pintype "passive"))
      (node (ref "R36") (pin "2") (pinfunction "2_2") (pintype "passive"))
    )
    (net (code "92") (name "3V3_DVDD") (class "Default")
      (node (ref "D10") (pin "1") (pinfunction "Vcca_1") (pintype "passive"))
      (node (ref "D10") (pin "4") (pinfunction "EN_4") (pintype "passive"))
      (node (ref "D11") (pin "8") (pinfunction "VCC_8") (pintype "power_in"))
      (node (ref "D12") (pin "3") (pinfunction "~{WP}_3") (pintype "passive"))
      (node (ref "D12") (pin "7") (pinfunction "~{HOLD}_7") (pintype "passive"))
      (node (ref "D12") (pin "8") (pinfunction "VDD_8") (pintype "passive"))
      (node (ref "D7") (pin "H7") (pinfunction "M0_0_H7") (pintype "input"))
      (node (ref "D7") (pin "M7") (pinfunction "CFGBVS_0_M7") (pintype "input"))
      (node (ref "H1") (pin "1") (pinfunction "A_1") (pintype "passive"))
      (node (ref "H1") (pin "2") (pinfunction "A_2") (pintype "passive"))
      (node (ref "H2") (pin "1") (pinfunction "A_1") (pintype "passive"))
      (node (ref "H2") (pin "2") (pinfunction "A_2") (pintype "passive"))
      (node (ref "H3") (pin "1") (pinfunction "A_1") (pintype "passive"))
      (node (ref "H3") (pin "2") (pinfunction "A_2") (pintype "passive"))
      (node (ref "R108") (pin "1") (pinfunction "1_1") (pintype "passive"))
      (node (ref "R109") (pin "1") (pinfunction "1_1") (pintype "passive"))
      (node (ref "R35") (pin "2") (pinfunction "2_2") (pintype "passive"))
      (node (ref "R37") (pin "2") (pinfunction "2_2") (pintype "passive"))
      (node (ref "R46") (pin "2") (pinfunction "2_2") (pintype "passive"))
      (node (ref "R47") (pin "2") (pinfunction "2_2") (pintype "passive"))
      (node (ref "R49") (pin "2") (pinfunction "2_2") (pintype "passive"))
      (node (ref "R53") (pin "2") (pinfunction "2_2") (pintype "passive"))
    )
    (net (code "93") (name "3V3_clk_avdd") (class "Default")
      (node (ref "C165") (pin "2") (pinfunction "2_2") (pintype "passive"))
      (node (ref "C176") (pin "2") (pinfunction "2_2") (pintype "passive"))
      (node (ref "C177") (pin "2") (pinfunction "2_2") (pintype "passive"))
      (node (ref "D14") (pin "3") (pinfunction "OUT_3") (pintype "passive"))
      (node (ref "L16") (pin "1") (pinfunction "1_1") (pintype "passive"))
    )
    (net (code "94") (name "6V") (class "Default")
      (node (ref "C162") (pin "2") (pinfunction "2_2") (pintype "passive"))
      (node (ref "C163") (pin "2") (pinfunction "2_2") (pintype "passive"))
      (node (ref "D10") (pin "6") (pinfunction "Vccy_6") (pintype "passive"))
      (node (ref "D14") (pin "1") (pinfunction "EN_1") (pintype "passive"))
      (node (ref "D14") (pin "4") (pinfunction "IN_4") (pintype "passive"))
    )
    (net (code "95") (name "AVDD_CLK") (class "Default")
      (node (ref "C156") (pin "1") (pinfunction "1_1") (pintype "passive"))
      (node (ref "C157") (pin "2") (pinfunction "2_2") (pintype "passive"))
      (node (ref "C158") (pin "1") (pinfunction "1_1") (pintype "passive"))
      (node (ref "C159") (pin "2") (pinfunction "2_2") (pintype "passive"))
      (node (ref "C160") (pin "1") (pinfunction "1_1") (pintype "passive"))
      (node (ref "C161") (pin "2") (pinfunction "2_2") (pintype "passive"))
      (node (ref "C164") (pin "1") (pinfunction "1_1") (pintype "passive"))
      (node (ref "C166") (pin "1") (pinfunction "1_1") (pintype "passive"))
      (node (ref "C168") (pin "1") (pinfunction "1_1") (pintype "passive"))
      (node (ref "C169") (pin "1") (pinfunction "1_1") (pintype "passive"))
      (node (ref "C170") (pin "1") (pinfunction "1_1") (pintype "passive"))
      (node (ref "C171") (pin "1") (pinfunction "1_1") (pintype "passive"))
      (node (ref "C172") (pin "1") (pinfunction "1_1") (pintype "passive"))
      (node (ref "C173") (pin "1") (pinfunction "1_1") (pintype "passive"))
      (node (ref "C174") (pin "1") (pinfunction "1_1") (pintype "passive"))
      (node (ref "C175") (pin "1") (pinfunction "1_1") (pintype "passive"))
      (node (ref "C178") (pin "2") (pinfunction "2_2") (pintype "passive"))
      (node (ref "C179") (pin "2") (pinfunction "2_2") (pintype "passive"))
      (node (ref "C180") (pin "2") (pinfunction "2_2") (pintype "passive"))
      (node (ref "C181") (pin "1") (pinfunction "1_1") (pintype "passive"))
      (node (ref "D8") (pin "1") (pinfunction "VS_1") (pintype "power_in"))
      (node (ref "D8") (pin "11") (pinfunction "VS_11") (pintype "power_in"))
      (node (ref "D8") (pin "12") (pinfunction "VS_12") (pintype "power_in"))
      (node (ref "D8") (pin "27") (pinfunction "VS_LVPECL_27") (pintype "power_in"))
      (node (ref "D8") (pin "30") (pinfunction "VS_30") (pintype "power_in"))
      (node (ref "D8") (pin "31") (pinfunction "VS_31") (pintype "power_in"))
      (node (ref "D8") (pin "32") (pinfunction "VS_32") (pintype "power_in"))
      (node (ref "D8") (pin "38") (pinfunction "VS_38") (pintype "power_in"))
      (node (ref "D8") (pin "4") (pinfunction "VCP_4") (pintype "power_in"))
      (node (ref "D8") (pin "41") (pinfunction "VS_LVPECL_41") (pintype "power_in"))
      (node (ref "D8") (pin "49") (pinfunction "VS_49") (pintype "power_in"))
      (node (ref "D8") (pin "50") (pinfunction "VS_50") (pintype "power_in"))
      (node (ref "D8") (pin "51") (pinfunction "VS_51") (pintype "power_in"))
      (node (ref "D8") (pin "54") (pinfunction "VS_LVPECL_54") (pintype "power_in"))
      (node (ref "D8") (pin "57") (pinfunction "VS_57") (pintype "power_in"))
      (node (ref "D8") (pin "60") (pinfunction "VS_60") (pintype "power_in"))
      (node (ref "D8") (pin "61") (pinfunction "VS_61") (pintype "power_in"))
      (node (ref "L16") (pin "2") (pinfunction "2_2") (pintype "passive"))
      (node (ref "Q1") (pin "4") (pinfunction "VDD_4") (pintype "passive"))
      (node (ref "R30") (pin "2") (pinfunction "2_2") (pintype "passive"))
    )
    (net (code "96") (name "DVDD_RAM") (class "Default")
      (node (ref "C144") (pin "2") (pinfunction "2_2") (pintype "passive"))
      (node (ref "C145") (pin "2") (pinfunction "2_2") (pintype "passive"))
      (node (ref "C146") (pin "2") (pinfunction "2_2") (pintype "passive"))
      (node (ref "C147") (pin "2") (pinfunction "2_2") (pintype "passive"))
      (node (ref "C148") (pin "2") (pinfunction "2_2") (pintype "passive"))
      (node (ref "C149") (pin "2") (pinfunction "2_2") (pintype "passive"))
      (node (ref "C150") (pin "2") (pinfunction "2_2") (pintype "passive"))
      (node (ref "C151") (pin "2") (pinfunction "2_2") (pintype "passive"))
      (node (ref "C152") (pin "2") (pinfunction "2_2") (pintype "passive"))
      (node (ref "C153") (pin "2") (pinfunction "2_2") (pintype "passive"))
      (node (ref "C154") (pin "2") (pinfunction "2_2") (pintype "passive"))
      (node (ref "C155") (pin "2") (pinfunction "2_2") (pintype "passive"))
      (node (ref "D13") (pin "11") (pinfunction "VDD_11") (pintype "passive"))
      (node (ref "D13") (pin "15") (pinfunction "VDD_15") (pintype "passive"))
      (node (ref "D13") (pin "20") (pinfunction "VDDQ_20") (pintype "passive"))
      (node (ref "D13") (pin "27") (pinfunction "VDDQ_27") (pintype "passive"))
      (node (ref "D13") (pin "4") (pinfunction "VDDQ_4") (pintype "passive"))
      (node (ref "D13") (pin "41") (pinfunction "VDD_41") (pintype "passive"))
      (node (ref "D13") (pin "54") (pinfunction "VDDQ_54") (pintype "passive"))
      (node (ref "D13") (pin "61") (pinfunction "VDDQ_61") (pintype "passive"))
      (node (ref "D13") (pin "65") (pinfunction "VDD_65") (pintype "passive"))
      (node (ref "D13") (pin "70") (pinfunction "VDDQ_70") (pintype "passive"))
      (node (ref "D13") (pin "77") (pinfunction "VDDQ_77") (pintype "passive"))
      (node (ref "D13") (pin "91") (pinfunction "VDD_91") (pintype "passive"))
      (node (ref "D13") (pin "97") (pinfunction "CE2_97") (pintype "passive"))
    )
    (net (code "97") (name "GND") (class "Default")
      (node (ref "C129") (pin "2") (pinfunction "2_2") (pintype "passive"))
      (node (ref "C131") (pin "2") (pinfunction "2_2") (pintype "passive"))
      (node (ref "C132") (pin "2") (pinfunction "2_2") (pintype "passive"))
      (node (ref "C133") (pin "2") (pinfunction "2_2") (pintype "passive"))
      (node (ref "C140") (pin "1") (pinfunction "1_1") (pintype "passive"))
      (node (ref "C141") (pin "1") (pinfunction "1_1") (pintype "passive"))
      (node (ref "C142") (pin "2") (pinfunction "2_2") (pintype "passive"))
      (node (ref "C143") (pin "2") (pinfunction "2_2") (pintype "passive"))
      (node (ref "C144") (pin "1") (pinfunction "1_1") (pintype "passive"))
      (node (ref "C145") (pin "1") (pinfunction "1_1") (pintype "passive"))
      (node (ref "C146") (pin "1") (pinfunction "1_1") (pintype "passive"))
      (node (ref "C147") (pin "1") (pinfunction "1_1") (pintype "passive"))
      (node (ref "C148") (pin "1") (pinfunction "1_1") (pintype "passive"))
      (node (ref "C149") (pin "1") (pinfunction "1_1") (pintype "passive"))
      (node (ref "C150") (pin "1") (pinfunction "1_1") (pintype "passive"))
      (node (ref "C151") (pin "1") (pinfunction "1_1") (pintype "passive"))
      (node (ref "C152") (pin "1") (pinfunction "1_1") (pintype "passive"))
      (node (ref "C153") (pin "1") (pinfunction "1_1") (pintype "passive"))
      (node (ref "C154") (pin "1") (pinfunction "1_1") (pintype "passive"))
      (node (ref "C155") (pin "1") (pinfunction "1_1") (pintype "passive"))
      (node (ref "C156") (pin "2") (pinfunction "2_2") (pintype "passive"))
      (node (ref "C157") (pin "1") (pinfunction "1_1") (pintype "passive"))
      (node (ref "C158") (pin "2") (pinfunction "2_2") (pintype "passive"))
      (node (ref "C159") (pin "1") (pinfunction "1_1") (pintype "passive"))
      (node (ref "C160") (pin "2") (pinfunction "2_2") (pintype "passive"))
      (node (ref "C161") (pin "1") (pinfunction "1_1") (pintype "passive"))
      (node (ref "C162") (pin "1") (pinfunction "1_1") (pintype "passive"))
      (node (ref "C163") (pin "1") (pinfunction "1_1") (pintype "passive"))
      (node (ref "C164") (pin "2") (pinfunction "2_2") (pintype "passive"))
      (node (ref "C165") (pin "1") (pinfunction "1_1") (pintype "passive"))
      (node (ref "C166") (pin "2") (pinfunction "2_2") (pintype "passive"))
      (node (ref "C167") (pin "1") (pinfunction "1_1") (pintype "passive"))
      (node (ref "C168") (pin "2") (pinfunction "2_2") (pintype "passive"))
      (node (ref "C169") (pin "2") (pinfunction "2_2") (pintype "passive"))
      (node (ref "C170") (pin "2") (pinfunction "2_2") (pintype "passive"))
      (node (ref "C171") (pin "2") (pinfunction "2_2") (pintype "passive"))
      (node (ref "C172") (pin "2") (pinfunction "2_2") (pintype "passive"))
      (node (ref "C173") (pin "2") (pinfunction "2_2") (pintype "passive"))
      (node (ref "C174") (pin "2") (pinfunction "2_2") (pintype "passive"))
      (node (ref "C175") (pin "2") (pinfunction "2_2") (pintype "passive"))
      (node (ref "C176") (pin "1") (pinfunction "1_1") (pintype "passive"))
      (node (ref "C177") (pin "1") (pinfunction "1_1") (pintype "passive"))
      (node (ref "C178") (pin "1") (pinfunction "1_1") (pintype "passive"))
      (node (ref "C179") (pin "1") (pinfunction "1_1") (pintype "passive"))
      (node (ref "C180") (pin "1") (pinfunction "1_1") (pintype "passive"))
      (node (ref "C181") (pin "2") (pinfunction "2_2") (pintype "passive"))
      (node (ref "D10") (pin "3") (pinfunction "GND_3") (pintype "passive"))
      (node (ref "D11") (pin "1") (pinfunction "A0_1") (pintype "passive"))
      (node (ref "D11") (pin "2") (pinfunction "A1_2") (pintype "passive"))
      (node (ref "D11") (pin "3") (pinfunction "A2_3") (pintype "passive"))
      (node (ref "D11") (pin "4") (pinfunction "VSS_4") (pintype "power_in"))
      (node (ref "D11") (pin "7") (pinfunction "NC_7") (pintype "passive"))
      (node (ref "D12") (pin "4") (pinfunction "VSS_4") (pintype "passive"))
      (node (ref "D13") (pin "17") (pinfunction "VSS_17") (pintype "passive"))
      (node (ref "D13") (pin "21") (pinfunction "VSS_21") (pintype "passive"))
      (node (ref "D13") (pin "26") (pinfunction "VSS_26") (pintype "passive"))
      (node (ref "D13") (pin "31") (pinfunction "MODE_31") (pintype "passive"))
      (node (ref "D13") (pin "40") (pinfunction "VSS_40") (pintype "passive"))
      (node (ref "D13") (pin "5") (pinfunction "VSS_5") (pintype "passive"))
      (node (ref "D13") (pin "55") (pinfunction "VSS_55") (pintype "passive"))
      (node (ref "D13") (pin "60") (pinfunction "VSS_60") (pintype "passive"))
      (node (ref "D13") (pin "64") (pinfunction "ZZ_64") (pintype "passive"))
      (node (ref "D13") (pin "67") (pinfunction "VSS_67") (pintype "passive"))
      (node (ref "D13") (pin "71") (pinfunction "VSS_71") (pintype "passive"))
      (node (ref "D13") (pin "76") (pinfunction "VSS_76") (pintype "passive"))
      (node (ref "D13") (pin "90") (pinfunction "VSS_90") (pintype "passive"))
      (node (ref "D13") (pin "92") (pinfunction "CE3_92") (pintype "passive"))
      (node (ref "D13") (pin "93") (pinfunction "BWA_93") (pintype "passive"))
      (node (ref "D13") (pin "94") (pinfunction "BWB_94") (pintype "passive"))
      (node (ref "D14") (pin "5") (pinfunction "GND_5") (pintype "passive"))
      (node (ref "D7") (pin "H6") (pinfunction "M1_0_H6") (pintype "input"))
      (node (ref "D7") (pin "J5") (pinfunction "M2_0_J5") (pintype "input"))
      (node (ref "D7") (pin "L11") (pinfunction "VREFN_0_L11") (pintype "input"))
      (node (ref "D7") (pin "L12") (pinfunction "VP_0_L12") (pintype "input"))
      (node (ref "D7") (pin "M11") (pinfunction "VN_0_M11") (pintype "input"))
      (node (ref "D7") (pin "M12") (pinfunction "VREFP_0_M12") (pintype "input"))
      (node (ref "D7") (pin "N11") (pinfunction "DXN_0_N11") (pintype "input"))
      (node (ref "D7") (pin "N12") (pinfunction "DXP_0_N12") (pintype "input"))
      (node (ref "D8") (pin "0") (pinfunction "EPAD_0") (pintype "power_in"))
      (node (ref "D8") (pin "37") (pinfunction "GND_37") (pintype "power_in"))
      (node (ref "D8") (pin "44") (pinfunction "GND_44") (pintype "power_in"))
      (node (ref "D8") (pin "59") (pinfunction "GND_59") (pintype "power_in"))
      (node (ref "D9") (pin "1") (pinfunction "A_1") (pintype "passive"))
      (node (ref "D9") (pin "2") (pinfunction "K_2") (pintype "passive"))
      (node (ref "Q1") (pin "2") (pinfunction "GND_2") (pintype "passive"))
      (node (ref "R33") (pin "1") (pinfunction "1_1") (pintype "passive"))
      (node (ref "R34") (pin "2") (pinfunction "2_2") (pintype "passive"))
      (node (ref "R36") (pin "1") (pinfunction "1_1") (pintype "passive"))
      (node (ref "R41") (pin "3") (pinfunction "3_3") (pintype "passive"))
      (node (ref "R41") (pin "4") (pinfunction "4_4") (pintype "passive"))
      (node (ref "R42") (pin "1") (pinfunction "1_1") (pintype "passive"))
      (node (ref "R44") (pin "3") (pinfunction "3_3") (pintype "passive"))
      (node (ref "R44") (pin "4") (pinfunction "4_4") (pintype "passive"))
      (node (ref "R48") (pin "3") (pinfunction "3_3") (pintype "passive"))
      (node (ref "R48") (pin "4") (pinfunction "4_4") (pintype "passive"))
      (node (ref "R50") (pin "3") (pinfunction "3_3") (pintype "passive"))
      (node (ref "R50") (pin "4") (pinfunction "4_4") (pintype "passive"))
      (node (ref "R60") (pin "1") (pinfunction "1_1") (pintype "passive"))
      (node (ref "R61") (pin "1") (pinfunction "1_1") (pintype "passive"))
      (node (ref "SB1") (pin "2") (pinfunction "2_2") (pintype "passive"))
      (node (ref "T1") (pin "2") (pinfunction "S_2") (pintype "passive"))
      (node (ref "X3") (pin "1") (pinfunction "GND_1") (pintype "passive"))
      (node (ref "X3") (pin "11") (pinfunction "GND_11") (pintype "passive"))
      (node (ref "X3") (pin "13") (pinfunction "GND_13") (pintype "passive"))
      (node (ref "X3") (pin "3") (pinfunction "GND_3") (pintype "passive"))
      (node (ref "X3") (pin "5") (pinfunction "GND_5") (pintype "passive"))
      (node (ref "X3") (pin "7") (pinfunction "GND_7") (pintype "passive"))
      (node (ref "X3") (pin "9") (pinfunction "GND_9") (pintype "passive"))
      (node (ref "X4") (pin "4") (pinfunction "TMS_4") (pintype "passive"))
      (node (ref "XW1") (pin "0") (pinfunction "GND_0") (pintype "power_in"))
      (node (ref "XW2") (pin "0") (pinfunction "GND_0") (pintype "power_in"))
    )
    (net (code "98") (name "Net-(C130-Pad2)") (class "Default")
      (node (ref "C130") (pin "2") (pinfunction "2_2") (pintype "passive"))
      (node (ref "D9") (pin "3") (pinfunction "K_3") (pintype "passive"))
      (node (ref "R29") (pin "2") (pinfunction "2_2") (pintype "passive"))
      (node (ref "R33") (pin "2") (pinfunction "2_2") (pintype "passive"))
    )
    (net (code "99") (name "Net-(C132-Pad1)") (class "Default")
      (node (ref "C132") (pin "1") (pinfunction "1_1") (pintype "passive"))
      (node (ref "R31") (pin "2") (pinfunction "2_2") (pintype "passive"))
    )
    (net (code "100") (name "Net-(C140-Pad2)") (class "Default")
      (node (ref "C140") (pin "2") (pinfunction "2_2") (pintype "passive"))
      (node (ref "R39") (pin "1") (pinfunction "1_1") (pintype "passive"))
    )
    (net (code "101") (name "Net-(D8B-CLK_N)") (class "Default")
      (node (ref "C143") (pin "1") (pinfunction "1_1") (pintype "passive"))
      (node (ref "D8") (pin "14") (pinfunction "CLK_N_14") (pintype "passive"))
    )
    (net (code "102") (name "Net-(D8B-REFIN_N)") (class "Default")
      (node (ref "C142") (pin "1") (pinfunction "1_1") (pintype "passive"))
      (node (ref "D8") (pin "63") (pinfunction "REFIN_N_63") (pintype "passive"))
    )
    (net (code "103") (name "Net-(D8C-OUT0_N)") (class "Default")
      (node (ref "D8") (pin "55") (pinfunction "OUT0_N_55") (pintype "output"))
      (node (ref "R40") (pin "2") (pinfunction "2_2") (pintype "passive"))
    )
    (net (code "104") (name "Net-(D8C-OUT0_P)") (class "Default")
      (node (ref "D8") (pin "56") (pinfunction "OUT0_P_56") (pintype "output"))
      (node (ref "R40") (pin "1") (pinfunction "1_1") (pintype "passive"))
    )
    (net (code "105") (name "Net-(D8C-OUT1_N)") (class "Default")
      (node (ref "C134") (pin "2") (pinfunction "2_2") (pintype "passive"))
      (node (ref "D8") (pin "52") (pinfunction "OUT1_N_52") (pintype "output"))
      (node (ref "R44") (pin "1") (pinfunction "1_1") (pintype "passive"))
    )
    (net (code "106") (name "Net-(D8C-OUT1_P)") (class "Default")
      (node (ref "C135") (pin "2") (pinfunction "2_2") (pintype "passive"))
      (node (ref "D8") (pin "53") (pinfunction "OUT1_P_53") (pintype "output"))
      (node (ref "R44") (pin "2") (pinfunction "2_2") (pintype "passive"))
    )
    (net (code "107") (name "Net-(D8C-OUT2_N)") (class "Default")
      (node (ref "C136") (pin "2") (pinfunction "2_2") (pintype "passive"))
      (node (ref "D8") (pin "42") (pinfunction "OUT2_N_42") (pintype "output"))
      (node (ref "R48") (pin "1") (pinfunction "1_1") (pintype "passive"))
    )
    (net (code "108") (name "Net-(D8C-OUT2_P)") (class "Default")
      (node (ref "C137") (pin "2") (pinfunction "2_2") (pintype "passive"))
      (node (ref "D8") (pin "43") (pinfunction "OUT2_P_43") (pintype "output"))
      (node (ref "R48") (pin "2") (pinfunction "2_2") (pintype "passive"))
    )
    (net (code "109") (name "Net-(D8C-OUT3_N)") (class "Default")
      (node (ref "C138") (pin "2") (pinfunction "2_2") (pintype "passive"))
      (node (ref "D8") (pin "39") (pinfunction "OUT3_N_39") (pintype "output"))
      (node (ref "R50") (pin "1") (pinfunction "1_1") (pintype "passive"))
    )
    (net (code "110") (name "Net-(D8C-OUT3_P)") (class "Default")
      (node (ref "C139") (pin "2") (pinfunction "2_2") (pintype "passive"))
      (node (ref "D8") (pin "40") (pinfunction "OUT3_P_40") (pintype "output"))
      (node (ref "R50") (pin "2") (pinfunction "2_2") (pintype "passive"))
    )
    (net (code "111") (name "Net-(D8D-OUT6_N)") (class "Default")
      (node (ref "D8") (pin "47") (pinfunction "OUT6_N_47") (pintype "output"))
      (node (ref "R54") (pin "2") (pinfunction "2_2") (pintype "passive"))
    )
    (net (code "112") (name "Net-(D8D-OUT6_P)") (class "Default")
      (node (ref "D8") (pin "48") (pinfunction "OUT6_P_48") (pintype "output"))
      (node (ref "R54") (pin "1") (pinfunction "1_1") (pintype "passive"))
    )
    (net (code "113") (name "Net-(D8D-OUT7_N)") (class "Default")
      (node (ref "D8") (pin "45") (pinfunction "OUT7_N_45") (pintype "output"))
      (node (ref "R57") (pin "2") (pinfunction "2_2") (pintype "passive"))
    )
    (net (code "114") (name "Net-(D8D-OUT7_P)") (class "Default")
      (node (ref "D8") (pin "46") (pinfunction "OUT7_P_46") (pintype "output"))
      (node (ref "R57") (pin "1") (pinfunction "1_1") (pintype "passive"))
    )
    (net (code "115") (name "Net-(D8E-BYPASS)") (class "Default")
      (node (ref "C167") (pin "2") (pinfunction "2_2") (pintype "passive"))
      (node (ref "D8") (pin "10") (pinfunction "BYPASS_10") (pintype "passive"))
    )
    (net (code "116") (name "Net-(D8E-CPRSET)") (class "Default")
      (node (ref "D8") (pin "62") (pinfunction "CPRSET_62") (pintype "passive"))
      (node (ref "R60") (pin "2") (pinfunction "2_2") (pintype "passive"))
    )
    (net (code "117") (name "Net-(D8E-RSET)") (class "Default")
      (node (ref "D8") (pin "58") (pinfunction "RSET_58") (pintype "passive"))
      (node (ref "R61") (pin "2") (pinfunction "2_2") (pintype "passive"))
    )
    (net (code "118") (name "Net-(D10-Y)") (class "Default")
      (node (ref "D10") (pin "5") (pinfunction "Y_5") (pintype "passive"))
      (node (ref "R38") (pin "1") (pinfunction "1_1") (pintype "passive"))
    )
    (net (code "119") (name "Net-(H1-K-Pad3)") (class "Default")
      (node (ref "H1") (pin "3") (pinfunction "K_3") (pintype "passive"))
      (node (ref "R45") (pin "1") (pinfunction "1_1") (pintype "passive"))
    )
    (net (code "120") (name "Net-(H1-K-Pad4)") (class "Default")
      (node (ref "H1") (pin "4") (pinfunction "K_4") (pintype "passive"))
      (node (ref "R43") (pin "1") (pinfunction "1_1") (pintype "passive"))
    )
    (net (code "121") (name "Net-(H2-K-Pad3)") (class "Default")
      (node (ref "H2") (pin "3") (pinfunction "K_3") (pintype "passive"))
      (node (ref "R52") (pin "1") (pinfunction "1_1") (pintype "passive"))
    )
    (net (code "122") (name "Net-(H2-K-Pad4)") (class "Default")
      (node (ref "H2") (pin "4") (pinfunction "K_4") (pintype "passive"))
      (node (ref "R51") (pin "1") (pinfunction "1_1") (pintype "passive"))
    )
    (net (code "123") (name "Net-(H3-K-Pad3)") (class "Default")
      (node (ref "H3") (pin "3") (pinfunction "K_3") (pintype "passive"))
      (node (ref "R59") (pin "1") (pinfunction "1_1") (pintype "passive"))
    )
    (net (code "124") (name "Net-(H3-K-Pad4)") (class "Default")
      (node (ref "H3") (pin "4") (pinfunction "K_4") (pintype "passive"))
      (node (ref "R55") (pin "1") (pinfunction "1_1") (pintype "passive"))
    )
    (net (code "125") (name "Net-(Q1-OUT)") (class "Default")
      (node (ref "Q1") (pin "3") (pinfunction "OUT_3") (pintype "output"))
      (node (ref "R34") (pin "1") (pinfunction "1_1") (pintype "passive"))
    )
    (net (code "126") (name "Net-(R58-Pad2)") (class "Default")
      (node (ref "R58") (pin "2") (pinfunction "2_2") (pintype "passive"))
      (node (ref "X4") (pin "3") (pinfunction "GND_3") (pintype "passive"))
    )
    (net (code "127") (name "Net-(R109-Pad2)") (class "Default")
      (node (ref "R109") (pin "2") (pinfunction "2_2") (pintype "passive"))
      (node (ref "X4") (pin "1") (pinfunction "GND_1") (pintype "passive"))
    )
    (net (code "128") (name "Net-(T1-D)") (class "Default")
      (node (ref "R43") (pin "2") (pinfunction "2_2") (pintype "passive"))
      (node (ref "T1") (pin "3") (pinfunction "D_3") (pintype "passive"))
    )
    (net (code "129") (name "Net-(X3-VREF)") (class "Default")
      (node (ref "R108") (pin "2") (pinfunction "2_2") (pintype "passive"))
      (node (ref "X3") (pin "2") (pinfunction "VREF_2") (pintype "passive"))
    )
    (net (code "130") (name "Net-(X4-VREF)") (class "Default")
      (node (ref "R56") (pin "2") (pinfunction "2_2") (pintype "passive"))
      (node (ref "X4") (pin "2") (pinfunction "VREF_2") (pintype "passive"))
    )
    (net (code "131") (name "Net-(XW1-RF)") (class "Default")
      (node (ref "R29") (pin "1") (pinfunction "1_1") (pintype "passive"))
      (node (ref "XW1") (pin "1") (pinfunction "RF_1") (pintype "passive"))
    )
    (net (code "132") (name "Net-(XW2-RF)") (class "Default")
      (node (ref "R38") (pin "2") (pinfunction "2_2") (pintype "passive"))
      (node (ref "R39") (pin "2") (pinfunction "2_2") (pintype "passive"))
      (node (ref "R42") (pin "2") (pinfunction "2_2") (pintype "passive"))
      (node (ref "XW2") (pin "1") (pinfunction "RF_1") (pintype "passive"))
    )
    (net (code "133") (name "unconnected-(D7C-IO_25_15-PadH15)") (class "Default")
      (node (ref "D7") (pin "H15") (pinfunction "IO_25_15_H15") (pintype "bidirectional"))
    )
    (net (code "134") (name "unconnected-(D7C-IO_L1N_T0_AD0N_15-PadG16)") (class "Default")
      (node (ref "D7") (pin "G16") (pinfunction "IO_L1N_T0_AD0N_15_G16") (pintype "bidirectional"))
    )
    (net (code "135") (name "unconnected-(D7C-IO_L12N_T1_MRCC_AD5N_15-PadC18)") (class "Default")
      (node (ref "D7") (pin "C18") (pinfunction "IO_L12N_T1_MRCC_AD5N_15_C18") (pintype "bidirectional+no_connect"))
    )
    (net (code "136") (name "unconnected-(D7C-IO_L13N_T2_MRCC_15-PadE18)") (class "Default")
      (node (ref "D7") (pin "E18") (pinfunction "IO_L13N_T2_MRCC_15_E18") (pintype "bidirectional"))
    )
    (net (code "137") (name "unconnected-(D7C-IO_L13P_T2_MRCC_15-PadE17)") (class "Default")
      (node (ref "D7") (pin "E17") (pinfunction "IO_L13P_T2_MRCC_15_E17") (pintype "bidirectional"))
    )
    (net (code "138") (name "unconnected-(D7C-IO_L16N_T2_A27_15-PadJ17)") (class "Default")
      (node (ref "D7") (pin "J17") (pinfunction "IO_L16N_T2_A27_15_J17") (pintype "bidirectional"))
    )
    (net (code "139") (name "unconnected-(D7C-IO_L16P_T2_A28_15-PadJ16)") (class "Default")
      (node (ref "D7") (pin "J16") (pinfunction "IO_L16P_T2_A28_15_J16") (pintype "bidirectional"))
    )
    (net (code "140") (name "unconnected-(D8A-PD-Pad24)") (class "Default")
      (node (ref "D8") (pin "24") (pinfunction "PD_24") (pintype "passive"))
    )
    (net (code "141") (name "unconnected-(D8A-REF_SEL-Pad7)") (class "Default")
      (node (ref "D8") (pin "7") (pinfunction "REF_SEL_7") (pintype "passive"))
    )
    (net (code "142") (name "unconnected-(D8B-LF-Pad9)") (class "Default")
      (node (ref "D8") (pin "9") (pinfunction "LF_9") (pintype "passive"))
    )
    (net (code "143") (name "unconnected-(D8C-OUT4_N-Pad26)") (class "Default")
      (node (ref "D8") (pin "26") (pinfunction "OUT4_N_26") (pintype "output"))
    )
    (net (code "144") (name "unconnected-(D8C-OUT4_P-Pad25)") (class "Default")
      (node (ref "D8") (pin "25") (pinfunction "OUT4_P_25") (pintype "output"))
    )
    (net (code "145") (name "unconnected-(D8C-OUT5_N-Pad29)") (class "Default")
      (node (ref "D8") (pin "29") (pinfunction "OUT5_N_29") (pintype "output"))
    )
    (net (code "146") (name "unconnected-(D8C-OUT5_P-Pad28)") (class "Default")
      (node (ref "D8") (pin "28") (pinfunction "OUT5_P_28") (pintype "output"))
    )
    (net (code "147") (name "unconnected-(D8D-OUT8_N-Pad34)") (class "Default")
      (node (ref "D8") (pin "34") (pinfunction "OUT8_N_34") (pintype "output+no_connect"))
    )
    (net (code "148") (name "unconnected-(D8D-OUT9_N-Pad36)") (class "Default")
      (node (ref "D8") (pin "36") (pinfunction "OUT9_N_36") (pintype "output"))
    )
    (net (code "149") (name "unconnected-(D8D-OUT9_P-Pad35)") (class "Default")
      (node (ref "D8") (pin "35") (pinfunction "OUT9_P_35") (pintype "output"))
    )
    (net (code "150") (name "unconnected-(D8E-NC-Pad15)") (class "Default")
      (node (ref "D8") (pin "15") (pinfunction "NC_15") (pintype "passive"))
    )
    (net (code "151") (name "unconnected-(D8E-NC-Pad18)") (class "Default")
      (node (ref "D8") (pin "18") (pinfunction "NC_18") (pintype "passive"))
    )
    (net (code "152") (name "unconnected-(D8E-NC-Pad19)") (class "Default")
      (node (ref "D8") (pin "19") (pinfunction "NC_19") (pintype "passive"))
    )
    (net (code "153") (name "unconnected-(D8E-NC-Pad20)") (class "Default")
      (node (ref "D8") (pin "20") (pinfunction "NC_20") (pintype "passive"))
    )
    (net (code "154") (name "unconnected-(D13C-NC-Pad1)") (class "Default")
      (node (ref "D13") (pin "1") (pinfunction "NC_1") (pintype "passive"))
    )
    (net (code "155") (name "unconnected-(D13C-NC-Pad2)") (class "Default")
      (node (ref "D13") (pin "2") (pinfunction "NC_2") (pintype "passive"))
    )
    (net (code "156") (name "unconnected-(D13C-NC-Pad3)") (class "Default")
      (node (ref "D13") (pin "3") (pinfunction "NC_3") (pintype "passive"))
    )
    (net (code "157") (name "unconnected-(D13C-NC-Pad6)") (class "Default")
      (node (ref "D13") (pin "6") (pinfunction "NC_6") (pintype "passive"))
    )
    (net (code "158") (name "unconnected-(D13C-NC-Pad7)") (class "Default")
      (node (ref "D13") (pin "7") (pinfunction "NC_7") (pintype "passive"))
    )
    (net (code "159") (name "unconnected-(D13C-NC-Pad10)") (class "Default")
      (node (ref "D13") (pin "10") (pinfunction "NC_10") (pintype "passive"))
    )
    (net (code "160") (name "unconnected-(D13C-NC-Pad14)") (class "Default")
      (node (ref "D13") (pin "14") (pinfunction "NC_14") (pintype "passive"))
    )
    (net (code "161") (name "unconnected-(D13C-NC-Pad16)") (class "Default")
      (node (ref "D13") (pin "16") (pinfunction "NC_16") (pintype "passive"))
    )
    (net (code "162") (name "unconnected-(D13C-NC-Pad25)") (class "Default")
      (node (ref "D13") (pin "25") (pinfunction "NC_25") (pintype "passive"))
    )
    (net (code "163") (name "unconnected-(D13C-NC-Pad28)") (class "Default")
      (node (ref "D13") (pin "28") (pinfunction "NC_28") (pintype "passive"))
    )
    (net (code "164") (name "unconnected-(D13C-NC-Pad29)") (class "Default")
      (node (ref "D13") (pin "29") (pinfunction "NC_29") (pintype "passive"))
    )
    (net (code "165") (name "unconnected-(D13C-NC-Pad30)") (class "Default")
      (node (ref "D13") (pin "30") (pinfunction "NC_30") (pintype "passive"))
    )
    (net (code "166") (name "unconnected-(D13C-NC-Pad38)") (class "Default")
      (node (ref "D13") (pin "38") (pinfunction "NC_38") (pintype "passive"))
    )
    (net (code "167") (name "unconnected-(D13C-NC-Pad39)") (class "Default")
      (node (ref "D13") (pin "39") (pinfunction "NC_39") (pintype "passive"))
    )
    (net (code "168") (name "unconnected-(D13C-NC-Pad42)") (class "Default")
      (node (ref "D13") (pin "42") (pinfunction "NC_42") (pintype "passive"))
    )
    (net (code "169") (name "unconnected-(D13C-NC-Pad43)") (class "Default")
      (node (ref "D13") (pin "43") (pinfunction "NC_43") (pintype "passive"))
    )
    (net (code "170") (name "unconnected-(D13C-NC-Pad51)") (class "Default")
      (node (ref "D13") (pin "51") (pinfunction "NC_51") (pintype "passive"))
    )
    (net (code "171") (name "unconnected-(D13C-NC-Pad52)") (class "Default")
      (node (ref "D13") (pin "52") (pinfunction "NC_52") (pintype "passive"))
    )
    (net (code "172") (name "unconnected-(D13C-NC-Pad53)") (class "Default")
      (node (ref "D13") (pin "53") (pinfunction "NC_53") (pintype "passive"))
    )
    (net (code "173") (name "unconnected-(D13C-NC-Pad56)") (class "Default")
      (node (ref "D13") (pin "56") (pinfunction "NC_56") (pintype "passive"))
    )
    (net (code "174") (name "unconnected-(D13C-NC-Pad57)") (class "Default")
      (node (ref "D13") (pin "57") (pinfunction "NC_57") (pintype "passive"))
    )
    (net (code "175") (name "unconnected-(D13C-NC-Pad66)") (class "Default")
      (node (ref "D13") (pin "66") (pinfunction "NC_66") (pintype "passive"))
    )
    (net (code "176") (name "unconnected-(D13C-NC-Pad75)") (class "Default")
      (node (ref "D13") (pin "75") (pinfunction "NC_75") (pintype "passive"))
    )
    (net (code "177") (name "unconnected-(D13C-NC-Pad78)") (class "Default")
      (node (ref "D13") (pin "78") (pinfunction "NC_78") (pintype "passive"))
    )
    (net (code "178") (name "unconnected-(D13C-NC-Pad79)") (class "Default")
      (node (ref "D13") (pin "79") (pinfunction "NC_79") (pintype "passive"))
    )
    (net (code "179") (name "unconnected-(D13C-NC-Pad84)") (class "Default")
      (node (ref "D13") (pin "84") (pinfunction "NC_84") (pintype "passive"))
    )
    (net (code "180") (name "unconnected-(D13C-NC-Pad95)") (class "Default")
      (node (ref "D13") (pin "95") (pinfunction "NC_95") (pintype "passive"))
    )
    (net (code "181") (name "unconnected-(D13C-NC-Pad96)") (class "Default")
      (node (ref "D13") (pin "96") (pinfunction "NC_96") (pintype "passive"))
    )
    (net (code "182") (name "unconnected-(D14-SNS*-Pad6)") (class "Default")
      (node (ref "D14") (pin "6") (pinfunction "SNS*_6") (pintype "passive"))
    )
    (net (code "183") (name "unconnected-(X3-NC-Pad12)") (class "Default")
      (node (ref "X3") (pin "12") (pinfunction "NC_12") (pintype "passive+no_connect"))
    )
    (net (code "184") (name "unconnected-(X3-NC-Pad14)") (class "Default")
      (node (ref "X3") (pin "14") (pinfunction "NC_14") (pintype "passive+no_connect"))
    )
  )
)
